# as14120_x31_fpga_power_conf.net
KiCad netlist of a schematic drawn in Altium Designer
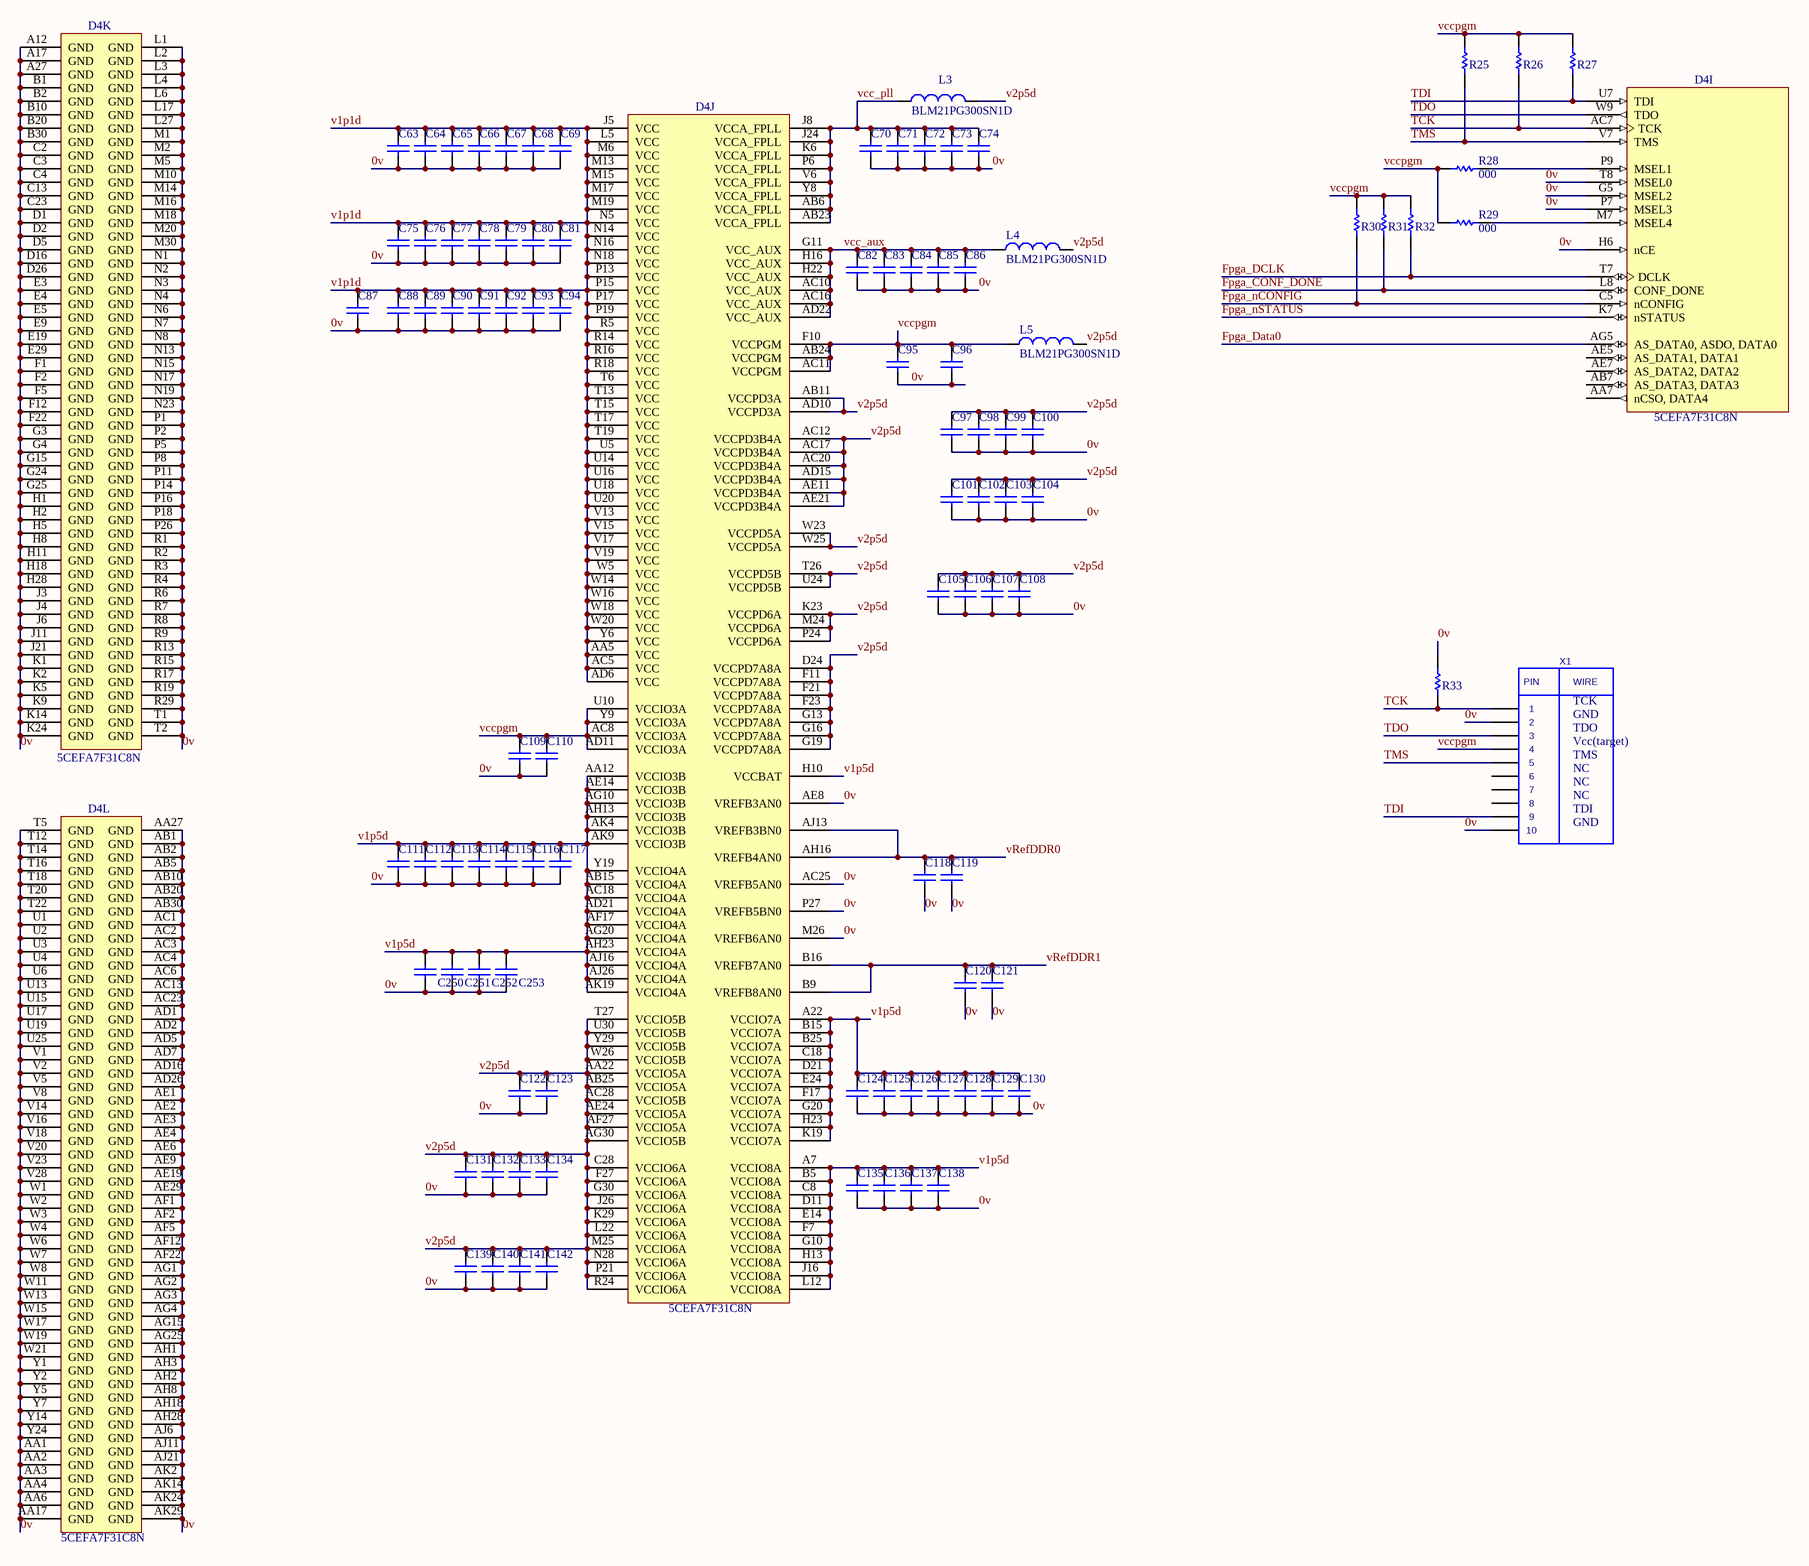
[diagram p0: as14120_x31_fpga_power_conf.SchDoc]

(export (version "E")
  (design (tool "Eeschema 10.0.6"))
  (components
    (comp (ref "C63")
      (value "CAP 1uF 10V 0402(1005)")
      (footprint "CAPC0402(1005)60_M")
      (description "CAP 1uF 10V ±20% 0402 (1005 Metric) Thickness 0.6mm SMD")
      (fields (field (name "TOLERANCE") "±20%"))
      (libsource (lib "as14120") (part "CAP_0402"))
    )
    (comp (ref "C64")
      (value "CAP 1uF 10V 0402(1005)")
      (footprint "CAPC0402(1005)60_M")
      (description "CAP 1uF 10V ±20% 0402 (1005 Metric) Thickness 0.6mm SMD")
      (fields (field (name "TOLERANCE") "±20%"))
      (libsource (lib "as14120") (part "CAP_0402"))
    )
    (comp (ref "C65")
      (value "CAP 1uF 10V 0402(1005)")
      (footprint "CAPC0402(1005)60_M")
      (description "CAP 1uF 10V ±20% 0402 (1005 Metric) Thickness 0.6mm SMD")
      (fields (field (name "TOLERANCE") "±20%"))
      (libsource (lib "as14120") (part "CAP_0402"))
    )
    (comp (ref "C66")
      (value "CAP 1uF 10V 0402(1005)")
      (footprint "CAPC0402(1005)60_M")
      (description "CAP 1uF 10V ±20% 0402 (1005 Metric) Thickness 0.6mm SMD")
      (fields (field (name "TOLERANCE") "±20%"))
      (libsource (lib "as14120") (part "CAP_0402"))
    )
    (comp (ref "C67")
      (value "CAP 1uF 10V 0402(1005)")
      (footprint "CAPC0402(1005)60_M")
      (description "CAP 1uF 10V ±20% 0402 (1005 Metric) Thickness 0.6mm SMD")
      (fields (field (name "TOLERANCE") "±20%"))
      (libsource (lib "as14120") (part "CAP_0402"))
    )
    (comp (ref "C68")
      (value "CAP 1uF 10V 0402(1005)")
      (footprint "CAPC0402(1005)60_M")
      (description "CAP 1uF 10V ±20% 0402 (1005 Metric) Thickness 0.6mm SMD")
      (fields (field (name "TOLERANCE") "±20%"))
      (libsource (lib "as14120") (part "CAP_0402"))
    )
    (comp (ref "C69")
      (value "CAP 1uF 10V 0402(1005)")
      (footprint "CAPC0402(1005)60_M")
      (description "CAP 1uF 10V ±20% 0402 (1005 Metric) Thickness 0.6mm SMD")
      (fields (field (name "TOLERANCE") "±20%"))
      (libsource (lib "as14120") (part "CAP_0402"))
    )
    (comp (ref "C70")
      (value "CAP 1uF 10V 0402(1005)")
      (footprint "CAPC0402(1005)60_M")
      (description "CAP 1uF 10V ±20% 0402 (1005 Metric) Thickness 0.6mm SMD")
      (fields (field (name "TOLERANCE") "±20%"))
      (libsource (lib "as14120") (part "CAP_0402"))
    )
    (comp (ref "C71")
      (value "CAP 1uF 10V 0402(1005)")
      (footprint "CAPC0402(1005)60_M")
      (description "CAP 1uF 10V ±20% 0402 (1005 Metric) Thickness 0.6mm SMD")
      (fields (field (name "TOLERANCE") "±20%"))
      (libsource (lib "as14120") (part "CAP_0402"))
    )
    (comp (ref "C72")
      (value "CAP 1uF 10V 0402(1005)")
      (footprint "CAPC0402(1005)60_M")
      (description "CAP 1uF 10V ±20% 0402 (1005 Metric) Thickness 0.6mm SMD")
      (fields (field (name "TOLERANCE") "±20%"))
      (libsource (lib "as14120") (part "CAP_0402"))
    )
    (comp (ref "C73")
      (value "CAP 1uF 10V 0402(1005)")
      (footprint "CAPC0402(1005)60_M")
      (description "CAP 1uF 10V ±20% 0402 (1005 Metric) Thickness 0.6mm SMD")
      (fields (field (name "TOLERANCE") "±20%"))
      (libsource (lib "as14120") (part "CAP_0402"))
    )
    (comp (ref "C74")
      (value "CAP 1uF 10V 0402(1005)")
      (footprint "CAPC0402(1005)60_M")
      (description "CAP 1uF 10V ±20% 0402 (1005 Metric) Thickness 0.6mm SMD")
      (fields (field (name "TOLERANCE") "±20%"))
      (libsource (lib "as14120") (part "CAP_0402"))
    )
    (comp (ref "C75")
      (value "CAP 1uF 10V 0402(1005)")
      (footprint "CAPC0402(1005)60_M")
      (description "CAP 1uF 10V ±20% 0402 (1005 Metric) Thickness 0.6mm SMD")
      (fields (field (name "TOLERANCE") "±20%"))
      (libsource (lib "as14120") (part "CAP_0402"))
    )
    (comp (ref "C76")
      (value "CAP 1uF 10V 0402(1005)")
      (footprint "CAPC0402(1005)60_M")
      (description "CAP 1uF 10V ±20% 0402 (1005 Metric) Thickness 0.6mm SMD")
      (fields (field (name "TOLERANCE") "±20%"))
      (libsource (lib "as14120") (part "CAP_0402"))
    )
    (comp (ref "C77")
      (value "CAP 1uF 10V 0402(1005)")
      (footprint "CAPC0402(1005)60_M")
      (description "CAP 1uF 10V ±20% 0402 (1005 Metric) Thickness 0.6mm SMD")
      (fields (field (name "TOLERANCE") "±20%"))
      (libsource (lib "as14120") (part "CAP_0402"))
    )
    (comp (ref "C78")
      (value "CAP 1uF 10V 0402(1005)")
      (footprint "CAPC0402(1005)60_M")
      (description "CAP 1uF 10V ±20% 0402 (1005 Metric) Thickness 0.6mm SMD")
      (fields (field (name "TOLERANCE") "±20%"))
      (libsource (lib "as14120") (part "CAP_0402"))
    )
    (comp (ref "C79")
      (value "CAP 1uF 10V 0402(1005)")
      (footprint "CAPC0402(1005)60_M")
      (description "CAP 1uF 10V ±20% 0402 (1005 Metric) Thickness 0.6mm SMD")
      (fields (field (name "TOLERANCE") "±20%"))
      (libsource (lib "as14120") (part "CAP_0402"))
    )
    (comp (ref "C80")
      (value "CAP 1uF 10V 0402(1005)")
      (footprint "CAPC0402(1005)60_M")
      (description "CAP 1uF 10V ±20% 0402 (1005 Metric) Thickness 0.6mm SMD")
      (fields (field (name "TOLERANCE") "±20%"))
      (libsource (lib "as14120") (part "CAP_0402"))
    )
    (comp (ref "C81")
      (value "CAP 1uF 10V 0402(1005)")
      (footprint "CAPC0402(1005)60_M")
      (description "CAP 1uF 10V ±20% 0402 (1005 Metric) Thickness 0.6mm SMD")
      (fields (field (name "TOLERANCE") "±20%"))
      (libsource (lib "as14120") (part "CAP_0402"))
    )
    (comp (ref "C82")
      (value "CAP 1uF 10V 0402(1005)")
      (footprint "CAPC0402(1005)60_M")
      (description "CAP 1uF 10V ±20% 0402 (1005 Metric) Thickness 0.6mm SMD")
      (fields (field (name "TOLERANCE") "±20%"))
      (libsource (lib "as14120") (part "CAP_0402"))
    )
    (comp (ref "C83")
      (value "CAP 1uF 10V 0402(1005)")
      (footprint "CAPC0402(1005)60_M")
      (description "CAP 1uF 10V ±20% 0402 (1005 Metric) Thickness 0.6mm SMD")
      (fields (field (name "TOLERANCE") "±20%"))
      (libsource (lib "as14120") (part "CAP_0402"))
    )
    (comp (ref "C84")
      (value "CAP 1uF 10V 0402(1005)")
      (footprint "CAPC0402(1005)60_M")
      (description "CAP 1uF 10V ±20% 0402 (1005 Metric) Thickness 0.6mm SMD")
      (fields (field (name "TOLERANCE") "±20%"))
      (libsource (lib "as14120") (part "CAP_0402"))
    )
    (comp (ref "C85")
      (value "CAP 1uF 10V 0402(1005)")
      (footprint "CAPC0402(1005)60_M")
      (description "CAP 1uF 10V ±20% 0402 (1005 Metric) Thickness 0.6mm SMD")
      (fields (field (name "TOLERANCE") "±20%"))
      (libsource (lib "as14120") (part "CAP_0402"))
    )
    (comp (ref "C86")
      (value "CAP 1uF 10V 0402(1005)")
      (footprint "CAPC0402(1005)60_M")
      (description "CAP 1uF 10V ±20% 0402 (1005 Metric) Thickness 0.6mm SMD")
      (fields (field (name "TOLERANCE") "±20%"))
      (libsource (lib "as14120") (part "CAP_0402"))
    )
    (comp (ref "C87")
      (value "CAP 1uF 10V 0402(1005)")
      (footprint "CAPC0402(1005)60_M")
      (description "CAP 1uF 10V ±20% 0402 (1005 Metric) Thickness 0.6mm SMD")
      (fields (field (name "TOLERANCE") "±20%"))
      (libsource (lib "as14120") (part "CAP_0402"))
    )
    (comp (ref "C88")
      (value "CAP 1uF 10V 0402(1005)")
      (footprint "CAPC0402(1005)60_M")
      (description "CAP 1uF 10V ±20% 0402 (1005 Metric) Thickness 0.6mm SMD")
      (fields (field (name "TOLERANCE") "±20%"))
      (libsource (lib "as14120") (part "CAP_0402"))
    )
    (comp (ref "C89")
      (value "CAP 1uF 10V 0402(1005)")
      (footprint "CAPC0402(1005)60_M")
      (description "CAP 1uF 10V ±20% 0402 (1005 Metric) Thickness 0.6mm SMD")
      (fields (field (name "TOLERANCE") "±20%"))
      (libsource (lib "as14120") (part "CAP_0402"))
    )
    (comp (ref "C90")
      (value "CAP 1uF 10V 0402(1005)")
      (footprint "CAPC0402(1005)60_M")
      (description "CAP 1uF 10V ±20% 0402 (1005 Metric) Thickness 0.6mm SMD")
      (fields (field (name "TOLERANCE") "±20%"))
      (libsource (lib "as14120") (part "CAP_0402"))
    )
    (comp (ref "C91")
      (value "CAP 1uF 10V 0402(1005)")
      (footprint "CAPC0402(1005)60_M")
      (description "CAP 1uF 10V ±20% 0402 (1005 Metric) Thickness 0.6mm SMD")
      (fields (field (name "TOLERANCE") "±20%"))
      (libsource (lib "as14120") (part "CAP_0402"))
    )
    (comp (ref "C92")
      (value "CAP 1uF 10V 0402(1005)")
      (footprint "CAPC0402(1005)60_M")
      (description "CAP 1uF 10V ±20% 0402 (1005 Metric) Thickness 0.6mm SMD")
      (fields (field (name "TOLERANCE") "±20%"))
      (libsource (lib "as14120") (part "CAP_0402"))
    )
    (comp (ref "C93")
      (value "CAP 1uF 10V 0402(1005)")
      (footprint "CAPC0402(1005)60_M")
      (description "CAP 1uF 10V ±20% 0402 (1005 Metric) Thickness 0.6mm SMD")
      (fields (field (name "TOLERANCE") "±20%"))
      (libsource (lib "as14120") (part "CAP_0402"))
    )
    (comp (ref "C94")
      (value "CAP 1uF 10V 0402(1005)")
      (footprint "CAPC0402(1005)60_M")
      (description "CAP 1uF 10V ±20% 0402 (1005 Metric) Thickness 0.6mm SMD")
      (fields (field (name "TOLERANCE") "±20%"))
      (libsource (lib "as14120") (part "CAP_0402"))
    )
    (comp (ref "C95")
      (value "CAP 1uF 10V 0402(1005)")
      (footprint "CAPC0402(1005)60_M")
      (description "CAP 1uF 10V ±20% 0402 (1005 Metric) Thickness 0.6mm SMD")
      (fields (field (name "TOLERANCE") "±20%"))
      (libsource (lib "as14120") (part "CAP_0402"))
    )
    (comp (ref "C96")
      (value "CAP 1uF 10V 0402(1005)")
      (footprint "CAPC0402(1005)60_M")
      (description "CAP 1uF 10V ±20% 0402 (1005 Metric) Thickness 0.6mm SMD")
      (fields (field (name "TOLERANCE") "±20%"))
      (libsource (lib "as14120") (part "CAP_0402"))
    )
    (comp (ref "C97")
      (value "CAP 1uF 10V 0402(1005)")
      (footprint "CAPC0402(1005)60_M")
      (description "CAP 1uF 10V ±20% 0402 (1005 Metric) Thickness 0.6mm SMD")
      (fields (field (name "TOLERANCE") "±20%"))
      (libsource (lib "as14120") (part "CAP_0402"))
    )
    (comp (ref "C98")
      (value "CAP 1uF 10V 0402(1005)")
      (footprint "CAPC0402(1005)60_M")
      (description "CAP 1uF 10V ±20% 0402 (1005 Metric) Thickness 0.6mm SMD")
      (fields (field (name "TOLERANCE") "±20%"))
      (libsource (lib "as14120") (part "CAP_0402"))
    )
    (comp (ref "C99")
      (value "CAP 1uF 10V 0402(1005)")
      (footprint "CAPC0402(1005)60_M")
      (description "CAP 1uF 10V ±20% 0402 (1005 Metric) Thickness 0.6mm SMD")
      (fields (field (name "TOLERANCE") "±20%"))
      (libsource (lib "as14120") (part "CAP_0402"))
    )
    (comp (ref "C100")
      (value "CAP 1uF 10V 0402(1005)")
      (footprint "CAPC0402(1005)60_M")
      (description "CAP 1uF 10V ±20% 0402 (1005 Metric) Thickness 0.6mm SMD")
      (fields (field (name "TOLERANCE") "±20%"))
      (libsource (lib "as14120") (part "CAP_0402"))
    )
    (comp (ref "C101")
      (value "CAP 1uF 10V 0402(1005)")
      (footprint "CAPC0402(1005)60_M")
      (description "CAP 1uF 10V ±20% 0402 (1005 Metric) Thickness 0.6mm SMD")
      (fields (field (name "TOLERANCE") "±20%"))
      (libsource (lib "as14120") (part "CAP_0402"))
    )
    (comp (ref "C102")
      (value "CAP 1uF 10V 0402(1005)")
      (footprint "CAPC0402(1005)60_M")
      (description "CAP 1uF 10V ±20% 0402 (1005 Metric) Thickness 0.6mm SMD")
      (fields (field (name "TOLERANCE") "±20%"))
      (libsource (lib "as14120") (part "CAP_0402"))
    )
    (comp (ref "C103")
      (value "CAP 1uF 10V 0402(1005)")
      (footprint "CAPC0402(1005)60_M")
      (description "CAP 1uF 10V ±20% 0402 (1005 Metric) Thickness 0.6mm SMD")
      (fields (field (name "TOLERANCE") "±20%"))
      (libsource (lib "as14120") (part "CAP_0402"))
    )
    (comp (ref "C104")
      (value "CAP 1uF 10V 0402(1005)")
      (footprint "CAPC0402(1005)60_M")
      (description "CAP 1uF 10V ±20% 0402 (1005 Metric) Thickness 0.6mm SMD")
      (fields (field (name "TOLERANCE") "±20%"))
      (libsource (lib "as14120") (part "CAP_0402"))
    )
    (comp (ref "C105")
      (value "CAP 1uF 10V 0402(1005)")
      (footprint "CAPC0402(1005)60_M")
      (description "CAP 1uF 10V ±20% 0402 (1005 Metric) Thickness 0.6mm SMD")
      (fields (field (name "TOLERANCE") "±20%"))
      (libsource (lib "as14120") (part "CAP_0402"))
    )
    (comp (ref "C106")
      (value "CAP 1uF 10V 0402(1005)")
      (footprint "CAPC0402(1005)60_M")
      (description "CAP 1uF 10V ±20% 0402 (1005 Metric) Thickness 0.6mm SMD")
      (fields (field (name "TOLERANCE") "±20%"))
      (libsource (lib "as14120") (part "CAP_0402"))
    )
    (comp (ref "C107")
      (value "CAP 1uF 10V 0402(1005)")
      (footprint "CAPC0402(1005)60_M")
      (description "CAP 1uF 10V ±20% 0402 (1005 Metric) Thickness 0.6mm SMD")
      (fields (field (name "TOLERANCE") "±20%"))
      (libsource (lib "as14120") (part "CAP_0402"))
    )
    (comp (ref "C108")
      (value "CAP 1uF 10V 0402(1005)")
      (footprint "CAPC0402(1005)60_M")
      (description "CAP 1uF 10V ±20% 0402 (1005 Metric) Thickness 0.6mm SMD")
      (fields (field (name "TOLERANCE") "±20%"))
      (libsource (lib "as14120") (part "CAP_0402"))
    )
    (comp (ref "C109")
      (value "CAP 1uF 10V 0402(1005)")
      (footprint "CAPC0402(1005)60_M")
      (description "CAP 1uF 10V ±20% 0402 (1005 Metric) Thickness 0.6mm SMD")
      (fields (field (name "TOLERANCE") "±20%"))
      (libsource (lib "as14120") (part "CAP_0402"))
    )
    (comp (ref "C110")
      (value "CAP 1uF 10V 0402(1005)")
      (footprint "CAPC0402(1005)60_M")
      (description "CAP 1uF 10V ±20% 0402 (1005 Metric) Thickness 0.6mm SMD")
      (fields (field (name "TOLERANCE") "±20%"))
      (libsource (lib "as14120") (part "CAP_0402"))
    )
    (comp (ref "C111")
      (value "CAP 1uF 10V 0402(1005)")
      (footprint "CAPC0402(1005)60_M")
      (description "CAP 1uF 10V ±20% 0402 (1005 Metric) Thickness 0.6mm SMD")
      (fields (field (name "TOLERANCE") "±20%"))
      (libsource (lib "as14120") (part "CAP_0402"))
    )
    (comp (ref "C112")
      (value "CAP 1uF 10V 0402(1005)")
      (footprint "CAPC0402(1005)60_M")
      (description "CAP 1uF 10V ±20% 0402 (1005 Metric) Thickness 0.6mm SMD")
      (fields (field (name "TOLERANCE") "±20%"))
      (libsource (lib "as14120") (part "CAP_0402"))
    )
    (comp (ref "C113")
      (value "CAP 1uF 10V 0402(1005)")
      (footprint "CAPC0402(1005)60_M")
      (description "CAP 1uF 10V ±20% 0402 (1005 Metric) Thickness 0.6mm SMD")
      (fields (field (name "TOLERANCE") "±20%"))
      (libsource (lib "as14120") (part "CAP_0402"))
    )
    (comp (ref "C114")
      (value "CAP 1uF 10V 0402(1005)")
      (footprint "CAPC0402(1005)60_M")
      (description "CAP 1uF 10V ±20% 0402 (1005 Metric) Thickness 0.6mm SMD")
      (fields (field (name "TOLERANCE") "±20%"))
      (libsource (lib "as14120") (part "CAP_0402"))
    )
    (comp (ref "C115")
      (value "CAP 1uF 10V 0402(1005)")
      (footprint "CAPC0402(1005)60_M")
      (description "CAP 1uF 10V ±20% 0402 (1005 Metric) Thickness 0.6mm SMD")
      (fields (field (name "TOLERANCE") "±20%"))
      (libsource (lib "as14120") (part "CAP_0402"))
    )
    (comp (ref "C116")
      (value "CAP 1uF 10V 0402(1005)")
      (footprint "CAPC0402(1005)60_M")
      (description "CAP 1uF 10V ±20% 0402 (1005 Metric) Thickness 0.6mm SMD")
      (fields (field (name "TOLERANCE") "±20%"))
      (libsource (lib "as14120") (part "CAP_0402"))
    )
    (comp (ref "C117")
      (value "CAP 1uF 10V 0402(1005)")
      (footprint "CAPC0402(1005)60_M")
      (description "CAP 1uF 10V ±20% 0402 (1005 Metric) Thickness 0.6mm SMD")
      (fields (field (name "TOLERANCE") "±20%"))
      (libsource (lib "as14120") (part "CAP_0402"))
    )
    (comp (ref "C118")
      (value "CAP 1uF 10V 0402(1005)")
      (footprint "CAPC0402(1005)60_M")
      (description "CAP 1uF 10V ±20% 0402 (1005 Metric) Thickness 0.6mm SMD")
      (fields (field (name "TOLERANCE") "±20%"))
      (libsource (lib "as14120") (part "CAP_0402"))
    )
    (comp (ref "C119")
      (value "CAP 1uF 10V 0402(1005)")
      (footprint "CAPC0402(1005)60_M")
      (description "CAP 1uF 10V ±20% 0402 (1005 Metric) Thickness 0.6mm SMD")
      (fields (field (name "TOLERANCE") "±20%"))
      (libsource (lib "as14120") (part "CAP_0402"))
    )
    (comp (ref "C120")
      (value "CAP 1uF 10V 0402(1005)")
      (footprint "CAPC0402(1005)60_M")
      (description "CAP 1uF 10V ±20% 0402 (1005 Metric) Thickness 0.6mm SMD")
      (fields (field (name "TOLERANCE") "±20%"))
      (libsource (lib "as14120") (part "CAP_0402"))
    )
    (comp (ref "C121")
      (value "CAP 1uF 10V 0402(1005)")
      (footprint "CAPC0402(1005)60_M")
      (description "CAP 1uF 10V ±20% 0402 (1005 Metric) Thickness 0.6mm SMD")
      (fields (field (name "TOLERANCE") "±20%"))
      (libsource (lib "as14120") (part "CAP_0402"))
    )
    (comp (ref "C122")
      (value "CAP 1uF 10V 0402(1005)")
      (footprint "CAPC0402(1005)60_M")
      (description "CAP 1uF 10V ±20% 0402 (1005 Metric) Thickness 0.6mm SMD")
      (fields (field (name "TOLERANCE") "±20%"))
      (libsource (lib "as14120") (part "CAP_0402"))
    )
    (comp (ref "C123")
      (value "CAP 1uF 10V 0402(1005)")
      (footprint "CAPC0402(1005)60_M")
      (description "CAP 1uF 10V ±20% 0402 (1005 Metric) Thickness 0.6mm SMD")
      (fields (field (name "TOLERANCE") "±20%"))
      (libsource (lib "as14120") (part "CAP_0402"))
    )
    (comp (ref "C124")
      (value "CAP 1uF 10V 0402(1005)")
      (footprint "CAPC0402(1005)60_M")
      (description "CAP 1uF 10V ±20% 0402 (1005 Metric) Thickness 0.6mm SMD")
      (fields (field (name "TOLERANCE") "±20%"))
      (libsource (lib "as14120") (part "CAP_0402"))
    )
    (comp (ref "C125")
      (value "CAP 1uF 10V 0402(1005)")
      (footprint "CAPC0402(1005)60_M")
      (description "CAP 1uF 10V ±20% 0402 (1005 Metric) Thickness 0.6mm SMD")
      (fields (field (name "TOLERANCE") "±20%"))
      (libsource (lib "as14120") (part "CAP_0402"))
    )
    (comp (ref "C126")
      (value "CAP 1uF 10V 0402(1005)")
      (footprint "CAPC0402(1005)60_M")
      (description "CAP 1uF 10V ±20% 0402 (1005 Metric) Thickness 0.6mm SMD")
      (fields (field (name "TOLERANCE") "±20%"))
      (libsource (lib "as14120") (part "CAP_0402"))
    )
    (comp (ref "C127")
      (value "CAP 1uF 10V 0402(1005)")
      (footprint "CAPC0402(1005)60_M")
      (description "CAP 1uF 10V ±20% 0402 (1005 Metric) Thickness 0.6mm SMD")
      (fields (field (name "TOLERANCE") "±20%"))
      (libsource (lib "as14120") (part "CAP_0402"))
    )
    (comp (ref "C128")
      (value "CAP 1uF 10V 0402(1005)")
      (footprint "CAPC0402(1005)60_M")
      (description "CAP 1uF 10V ±20% 0402 (1005 Metric) Thickness 0.6mm SMD")
      (fields (field (name "TOLERANCE") "±20%"))
      (libsource (lib "as14120") (part "CAP_0402"))
    )
    (comp (ref "C129")
      (value "CAP 1uF 10V 0402(1005)")
      (footprint "CAPC0402(1005)60_M")
      (description "CAP 1uF 10V ±20% 0402 (1005 Metric) Thickness 0.6mm SMD")
      (fields (field (name "TOLERANCE") "±20%"))
      (libsource (lib "as14120") (part "CAP_0402"))
    )
    (comp (ref "C130")
      (value "CAP 1uF 10V 0402(1005)")
      (footprint "CAPC0402(1005)60_M")
      (description "CAP 1uF 10V ±20% 0402 (1005 Metric) Thickness 0.6mm SMD")
      (fields (field (name "TOLERANCE") "±20%"))
      (libsource (lib "as14120") (part "CAP_0402"))
    )
    (comp (ref "C131")
      (value "CAP 1uF 10V 0402(1005)")
      (footprint "CAPC0402(1005)60_M")
      (description "CAP 1uF 10V ±20% 0402 (1005 Metric) Thickness 0.6mm SMD")
      (fields (field (name "TOLERANCE") "±20%"))
      (libsource (lib "as14120") (part "CAP_0402"))
    )
    (comp (ref "C132")
      (value "CAP 1uF 10V 0402(1005)")
      (footprint "CAPC0402(1005)60_M")
      (description "CAP 1uF 10V ±20% 0402 (1005 Metric) Thickness 0.6mm SMD")
      (fields (field (name "TOLERANCE") "±20%"))
      (libsource (lib "as14120") (part "CAP_0402"))
    )
    (comp (ref "C133")
      (value "CAP 1uF 10V 0402(1005)")
      (footprint "CAPC0402(1005)60_M")
      (description "CAP 1uF 10V ±20% 0402 (1005 Metric) Thickness 0.6mm SMD")
      (fields (field (name "TOLERANCE") "±20%"))
      (libsource (lib "as14120") (part "CAP_0402"))
    )
    (comp (ref "C134")
      (value "CAP 1uF 10V 0402(1005)")
      (footprint "CAPC0402(1005)60_M")
      (description "CAP 1uF 10V ±20% 0402 (1005 Metric) Thickness 0.6mm SMD")
      (fields (field (name "TOLERANCE") "±20%"))
      (libsource (lib "as14120") (part "CAP_0402"))
    )
    (comp (ref "C135")
      (value "CAP 1uF 10V 0402(1005)")
      (footprint "CAPC0402(1005)60_M")
      (description "CAP 1uF 10V ±20% 0402 (1005 Metric) Thickness 0.6mm SMD")
      (fields (field (name "TOLERANCE") "±20%"))
      (libsource (lib "as14120") (part "CAP_0402"))
    )
    (comp (ref "C136")
      (value "CAP 1uF 10V 0402(1005)")
      (footprint "CAPC0402(1005)60_M")
      (description "CAP 1uF 10V ±20% 0402 (1005 Metric) Thickness 0.6mm SMD")
      (fields (field (name "TOLERANCE") "±20%"))
      (libsource (lib "as14120") (part "CAP_0402"))
    )
    (comp (ref "C137")
      (value "CAP 1uF 10V 0402(1005)")
      (footprint "CAPC0402(1005)60_M")
      (description "CAP 1uF 10V ±20% 0402 (1005 Metric) Thickness 0.6mm SMD")
      (fields (field (name "TOLERANCE") "±20%"))
      (libsource (lib "as14120") (part "CAP_0402"))
    )
    (comp (ref "C138")
      (value "CAP 1uF 10V 0402(1005)")
      (footprint "CAPC0402(1005)60_M")
      (description "CAP 1uF 10V ±20% 0402 (1005 Metric) Thickness 0.6mm SMD")
      (fields (field (name "TOLERANCE") "±20%"))
      (libsource (lib "as14120") (part "CAP_0402"))
    )
    (comp (ref "C139")
      (value "CAP 1uF 10V 0402(1005)")
      (footprint "CAPC0402(1005)60_M")
      (description "CAP 1uF 10V ±20% 0402 (1005 Metric) Thickness 0.6mm SMD")
      (fields (field (name "TOLERANCE") "±20%"))
      (libsource (lib "as14120") (part "CAP_0402"))
    )
    (comp (ref "C140")
      (value "CAP 1uF 10V 0402(1005)")
      (footprint "CAPC0402(1005)60_M")
      (description "CAP 1uF 10V ±20% 0402 (1005 Metric) Thickness 0.6mm SMD")
      (fields (field (name "TOLERANCE") "±20%"))
      (libsource (lib "as14120") (part "CAP_0402"))
    )
    (comp (ref "C141")
      (value "CAP 1uF 10V 0402(1005)")
      (footprint "CAPC0402(1005)60_M")
      (description "CAP 1uF 10V ±20% 0402 (1005 Metric) Thickness 0.6mm SMD")
      (fields (field (name "TOLERANCE") "±20%"))
      (libsource (lib "as14120") (part "CAP_0402"))
    )
    (comp (ref "C142")
      (value "CAP 1uF 10V 0402(1005)")
      (footprint "CAPC0402(1005)60_M")
      (description "CAP 1uF 10V ±20% 0402 (1005 Metric) Thickness 0.6mm SMD")
      (fields (field (name "TOLERANCE") "±20%"))
      (libsource (lib "as14120") (part "CAP_0402"))
    )
    (comp (ref "C250")
      (value "CAP 1uF 10V 0402(1005)")
      (footprint "CAPC0402(1005)60_M")
      (description "CAP 1uF 10V ±20% 0402 (1005 Metric) Thickness 0.6mm SMD")
      (fields (field (name "TOLERANCE") "±20%"))
      (libsource (lib "as14120") (part "CAP_0402"))
    )
    (comp (ref "C251")
      (value "CAP 1uF 10V 0402(1005)")
      (footprint "CAPC0402(1005)60_M")
      (description "CAP 1uF 10V ±20% 0402 (1005 Metric) Thickness 0.6mm SMD")
      (fields (field (name "TOLERANCE") "±20%"))
      (libsource (lib "as14120") (part "CAP_0402"))
    )
    (comp (ref "C252")
      (value "CAP 1uF 10V 0402(1005)")
      (footprint "CAPC0402(1005)60_M")
      (description "CAP 1uF 10V ±20% 0402 (1005 Metric) Thickness 0.6mm SMD")
      (fields (field (name "TOLERANCE") "±20%"))
      (libsource (lib "as14120") (part "CAP_0402"))
    )
    (comp (ref "C253")
      (value "CAP 1uF 10V 0402(1005)")
      (footprint "CAPC0402(1005)60_M")
      (description "CAP 1uF 10V ±20% 0402 (1005 Metric) Thickness 0.6mm SMD")
      (fields (field (name "TOLERANCE") "±20%"))
      (libsource (lib "as14120") (part "CAP_0402"))
    )
    (comp (ref "D4")
      (value "5CEFA7F31C8N")
      (footprint "ALTR-896-FBGA-2000A")
      (fields (field (name "MANUFACTURER") "Altera"))
      (libsource (lib "Altera Cyclone V E") (part "5CEFA7F31C8N"))
    )
    (comp (ref "L3")
      (value "BLM21PG300SN1D")
      (footprint "CAPC0805(2012)100_N")
      (libsource (lib "as14120") (part "Ferrite_beat"))
    )
    (comp (ref "L4")
      (value "BLM21PG300SN1D")
      (footprint "CAPC0805(2012)100_N")
      (libsource (lib "as14120") (part "Ferrite_beat"))
    )
    (comp (ref "L5")
      (value "BLM21PG300SN1D")
      (footprint "CAPC0805(2012)100_N")
      (libsource (lib "as14120") (part "Ferrite_beat"))
    )
    (comp (ref "R25")
      (value "1K 5% 0603(1608)")
      (footprint "RESC0603(1608)_L")
      (description "1K 0.1W 5% 0603 (1608 Metric)  SMD")
      (fields (field (name "TOLERANCE") "5 %") (field (name "POWER") "0.1 W"))
      (libsource (lib "as14120") (part "RES_0603"))
    )
    (comp (ref "R26")
      (value "1K 5% 0603(1608)")
      (footprint "RESC0603(1608)_L")
      (description "1K 0.1W 5% 0603 (1608 Metric)  SMD")
      (fields (field (name "TOLERANCE") "5 %") (field (name "POWER") "0.1 W"))
      (libsource (lib "as14120") (part "RES_0603"))
    )
    (comp (ref "R27")
      (value "1K 5% 0603(1608)")
      (footprint "RESC0603(1608)_L")
      (description "1K 0.1W 5% 0603 (1608 Metric)  SMD")
      (fields (field (name "TOLERANCE") "5 %") (field (name "POWER") "0.1 W"))
      (libsource (lib "as14120") (part "RES_0603"))
    )
    (comp (ref "R28")
      (value "000")
      (footprint "RESC0603(1608)_L")
      (description "1K 0.1W 5% 0603 (1608 Metric)  SMD")
      (fields (field (name "TOLERANCE") "5 %") (field (name "POWER") "0.1 W"))
      (libsource (lib "as14120") (part "RES_0603"))
    )
    (comp (ref "R29")
      (value "000")
      (footprint "RESC0603(1608)_L")
      (description "1K 0.1W 5% 0603 (1608 Metric)  SMD")
      (fields (field (name "TOLERANCE") "5 %") (field (name "POWER") "0.1 W"))
      (libsource (lib "as14120") (part "RES_0603"))
    )
    (comp (ref "R30")
      (value "1K 5% 0603(1608)")
      (footprint "RESC0603(1608)_L")
      (description "1K 0.1W 5% 0603 (1608 Metric)  SMD")
      (fields (field (name "TOLERANCE") "5 %") (field (name "POWER") "0.1 W"))
      (libsource (lib "as14120") (part "RES_0603"))
    )
    (comp (ref "R31")
      (value "1K 5% 0603(1608)")
      (footprint "RESC0603(1608)_L")
      (description "1K 0.1W 5% 0603 (1608 Metric)  SMD")
      (fields (field (name "TOLERANCE") "5 %") (field (name "POWER") "0.1 W"))
      (libsource (lib "as14120") (part "RES_0603"))
    )
    (comp (ref "R32")
      (value "1K 5% 0603(1608)")
      (footprint "RESC0603(1608)_L")
      (description "1K 0.1W 5% 0603 (1608 Metric)  SMD")
      (fields (field (name "TOLERANCE") "5 %") (field (name "POWER") "0.1 W"))
      (libsource (lib "as14120") (part "RES_0603"))
    )
    (comp (ref "R33")
      (value "1K 5% 0603(1608)")
      (footprint "RESC0603(1608)_L")
      (description "1K 0.1W 5% 0603 (1608 Metric)  SMD")
      (fields (field (name "TOLERANCE") "5 %") (field (name "POWER") "0.1 W"))
      (libsource (lib "as14120") (part "RES_0603"))
    )
    (comp (ref "X1") (value "IDC10") (footprint "IDC10M") (libsource (lib "alexsb") (part "IDC10")))
  )
  (nets
    (net (code "1") (name "/0v") (class "Default")
      (node (ref "C100") (pin "1") (pinfunction "1_1") (pintype "passive"))
      (node (ref "C101") (pin "1") (pinfunction "1_1") (pintype "passive"))
      (node (ref "C102") (pin "1") (pinfunction "1_1") (pintype "passive"))
      (node (ref "C103") (pin "1") (pinfunction "1_1") (pintype "passive"))
      (node (ref "C104") (pin "1") (pinfunction "1_1") (pintype "passive"))
      (node (ref "C105") (pin "1") (pinfunction "1_1") (pintype "passive"))
      (node (ref "C106") (pin "1") (pinfunction "1_1") (pintype "passive"))
      (node (ref "C107") (pin "1") (pinfunction "1_1") (pintype "passive"))
      (node (ref "C108") (pin "1") (pinfunction "1_1") (pintype "passive"))
      (node (ref "C109") (pin "1") (pinfunction "1_1") (pintype "passive"))
      (node (ref "C110") (pin "1") (pinfunction "1_1") (pintype "passive"))
      (node (ref "C111") (pin "1") (pinfunction "1_1") (pintype "passive"))
      (node (ref "C112") (pin "1") (pinfunction "1_1") (pintype "passive"))
      (node (ref "C113") (pin "1") (pinfunction "1_1") (pintype "passive"))
      (node (ref "C114") (pin "1") (pinfunction "1_1") (pintype "passive"))
      (node (ref "C115") (pin "1") (pinfunction "1_1") (pintype "passive"))
      (node (ref "C116") (pin "1") (pinfunction "1_1") (pintype "passive"))
      (node (ref "C117") (pin "1") (pinfunction "1_1") (pintype "passive"))
      (node (ref "C118") (pin "1") (pinfunction "1_1") (pintype "passive"))
      (node (ref "C119") (pin "1") (pinfunction "1_1") (pintype "passive"))
      (node (ref "C120") (pin "1") (pinfunction "1_1") (pintype "passive"))
      (node (ref "C121") (pin "1") (pinfunction "1_1") (pintype "passive"))
      (node (ref "C122") (pin "1") (pinfunction "1_1") (pintype "passive"))
      (node (ref "C123") (pin "1") (pinfunction "1_1") (pintype "passive"))
      (node (ref "C124") (pin "1") (pinfunction "1_1") (pintype "passive"))
      (node (ref "C125") (pin "1") (pinfunction "1_1") (pintype "passive"))
      (node (ref "C126") (pin "1") (pinfunction "1_1") (pintype "passive"))
      (node (ref "C127") (pin "1") (pinfunction "1_1") (pintype "passive"))
      (node (ref "C128") (pin "1") (pinfunction "1_1") (pintype "passive"))
      (node (ref "C129") (pin "1") (pinfunction "1_1") (pintype "passive"))
      (node (ref "C130") (pin "1") (pinfunction "1_1") (pintype "passive"))
      (node (ref "C131") (pin "1") (pinfunction "1_1") (pintype "passive"))
      (node (ref "C132") (pin "1") (pinfunction "1_1") (pintype "passive"))
      (node (ref "C133") (pin "1") (pinfunction "1_1") (pintype "passive"))
      (node (ref "C134") (pin "1") (pinfunction "1_1") (pintype "passive"))
      (node (ref "C135") (pin "1") (pinfunction "1_1") (pintype "passive"))
      (node (ref "C136") (pin "1") (pinfunction "1_1") (pintype "passive"))
      (node (ref "C137") (pin "1") (pinfunction "1_1") (pintype "passive"))
      (node (ref "C138") (pin "1") (pinfunction "1_1") (pintype "passive"))
      (node (ref "C139") (pin "1") (pinfunction "1_1") (pintype "passive"))
      (node (ref "C140") (pin "1") (pinfunction "1_1") (pintype "passive"))
      (node (ref "C141") (pin "1") (pinfunction "1_1") (pintype "passive"))
      (node (ref "C142") (pin "1") (pinfunction "1_1") (pintype "passive"))
      (node (ref "C250") (pin "1") (pinfunction "1_1") (pintype "passive"))
      (node (ref "C251") (pin "1") (pinfunction "1_1") (pintype "passive"))
      (node (ref "C252") (pin "1") (pinfunction "1_1") (pintype "passive"))
      (node (ref "C253") (pin "1") (pinfunction "1_1") (pintype "passive"))
      (node (ref "C63") (pin "1") (pinfunction "1_1") (pintype "passive"))
      (node (ref "C64") (pin "1") (pinfunction "1_1") (pintype "passive"))
      (node (ref "C65") (pin "1") (pinfunction "1_1") (pintype "passive"))
      (node (ref "C66") (pin "1") (pinfunction "1_1") (pintype "passive"))
      (node (ref "C67") (pin "1") (pinfunction "1_1") (pintype "passive"))
      (node (ref "C68") (pin "1") (pinfunction "1_1") (pintype "passive"))
      (node (ref "C69") (pin "1") (pinfunction "1_1") (pintype "passive"))
      (node (ref "C70") (pin "1") (pinfunction "1_1") (pintype "passive"))
      (node (ref "C71") (pin "1") (pinfunction "1_1") (pintype "passive"))
      (node (ref "C72") (pin "1") (pinfunction "1_1") (pintype "passive"))
      (node (ref "C73") (pin "1") (pinfunction "1_1") (pintype "passive"))
      (node (ref "C74") (pin "1") (pinfunction "1_1") (pintype "passive"))
      (node (ref "C75") (pin "1") (pinfunction "1_1") (pintype "passive"))
      (node (ref "C76") (pin "1") (pinfunction "1_1") (pintype "passive"))
      (node (ref "C77") (pin "1") (pinfunction "1_1") (pintype "passive"))
      (node (ref "C78") (pin "1") (pinfunction "1_1") (pintype "passive"))
      (node (ref "C79") (pin "1") (pinfunction "1_1") (pintype "passive"))
      (node (ref "C80") (pin "1") (pinfunction "1_1") (pintype "passive"))
      (node (ref "C81") (pin "1") (pinfunction "1_1") (pintype "passive"))
      (node (ref "C82") (pin "1") (pinfunction "1_1") (pintype "passive"))
      (node (ref "C83") (pin "1") (pinfunction "1_1") (pintype "passive"))
      (node (ref "C84") (pin "1") (pinfunction "1_1") (pintype "passive"))
      (node (ref "C85") (pin "1") (pinfunction "1_1") (pintype "passive"))
      (node (ref "C86") (pin "1") (pinfunction "1_1") (pintype "passive"))
      (node (ref "C87") (pin "1") (pinfunction "1_1") (pintype "passive"))
      (node (ref "C88") (pin "1") (pinfunction "1_1") (pintype "passive"))
      (node (ref "C89") (pin "1") (pinfunction "1_1") (pintype "passive"))
      (node (ref "C90") (pin "1") (pinfunction "1_1") (pintype "passive"))
      (node (ref "C91") (pin "1") (pinfunction "1_1") (pintype "passive"))
      (node (ref "C92") (pin "1") (pinfunction "1_1") (pintype "passive"))
      (node (ref "C93") (pin "1") (pinfunction "1_1") (pintype "passive"))
      (node (ref "C94") (pin "1") (pinfunction "1_1") (pintype "passive"))
      (node (ref "C95") (pin "1") (pinfunction "1_1") (pintype "passive"))
      (node (ref "C96") (pin "1") (pinfunction "1_1") (pintype "passive"))
      (node (ref "C97") (pin "1") (pinfunction "1_1") (pintype "passive"))
      (node (ref "C98") (pin "1") (pinfunction "1_1") (pintype "passive"))
      (node (ref "C99") (pin "1") (pinfunction "1_1") (pintype "passive"))
      (node (ref "D4") (pin "A12") (pinfunction "GND_A12") (pintype "power_in"))
      (node (ref "D4") (pin "A17") (pinfunction "GND_A17") (pintype "power_in"))
      (node (ref "D4") (pin "A27") (pinfunction "GND_A27") (pintype "power_in"))
      (node (ref "D4") (pin "AA1") (pinfunction "GND_AA1") (pintype "power_in"))
      (node (ref "D4") (pin "AA17") (pinfunction "GND_AA17") (pintype "power_in"))
      (node (ref "D4") (pin "AA2") (pinfunction "GND_AA2") (pintype "power_in"))
      (node (ref "D4") (pin "AA27") (pinfunction "GND_AA27") (pintype "power_in"))
      (node (ref "D4") (pin "AA3") (pinfunction "GND_AA3") (pintype "power_in"))
      (node (ref "D4") (pin "AA4") (pinfunction "GND_AA4") (pintype "power_in"))
      (node (ref "D4") (pin "AA6") (pinfunction "GND_AA6") (pintype "power_in"))
      (node (ref "D4") (pin "AB1") (pinfunction "GND_AB1") (pintype "power_in"))
      (node (ref "D4") (pin "AB10") (pinfunction "GND_AB10") (pintype "power_in"))
      (node (ref "D4") (pin "AB2") (pinfunction "GND_AB2") (pintype "power_in"))
      (node (ref "D4") (pin "AB20") (pinfunction "GND_AB20") (pintype "power_in"))
      (node (ref "D4") (pin "AB30") (pinfunction "GND_AB30") (pintype "power_in"))
      (node (ref "D4") (pin "AB5") (pinfunction "GND_AB5") (pintype "power_in"))
      (node (ref "D4") (pin "AC1") (pinfunction "GND_AC1") (pintype "power_in"))
      (node (ref "D4") (pin "AC13") (pinfunction "GND_AC13") (pintype "power_in"))
      (node (ref "D4") (pin "AC2") (pinfunction "GND_AC2") (pintype "power_in"))
      (node (ref "D4") (pin "AC23") (pinfunction "GND_AC23") (pintype "power_in"))
      (node (ref "D4") (pin "AC25") (pinfunction "VREFB5AN0_AC25") (pintype "power_in"))
      (node (ref "D4") (pin "AC3") (pinfunction "GND_AC3") (pintype "power_in"))
      (node (ref "D4") (pin "AC4") (pinfunction "GND_AC4") (pintype "power_in"))
      (node (ref "D4") (pin "AC6") (pinfunction "GND_AC6") (pintype "power_in"))
      (node (ref "D4") (pin "AD1") (pinfunction "GND_AD1") (pintype "power_in"))
      (node (ref "D4") (pin "AD16") (pinfunction "GND_AD16") (pintype "power_in"))
      (node (ref "D4") (pin "AD2") (pinfunction "GND_AD2") (pintype "power_in"))
      (node (ref "D4") (pin "AD26") (pinfunction "GND_AD26") (pintype "power_in"))
      (node (ref "D4") (pin "AD5") (pinfunction "GND_AD5") (pintype "power_in"))
      (node (ref "D4") (pin "AD7") (pinfunction "GND_AD7") (pintype "power_in"))
      (node (ref "D4") (pin "AE1") (pinfunction "GND_AE1") (pintype "power_in"))
      (node (ref "D4") (pin "AE19") (pinfunction "GND_AE19") (pintype "power_in"))
      (node (ref "D4") (pin "AE2") (pinfunction "GND_AE2") (pintype "power_in"))
      (node (ref "D4") (pin "AE29") (pinfunction "GND_AE29") (pintype "power_in"))
      (node (ref "D4") (pin "AE3") (pinfunction "GND_AE3") (pintype "power_in"))
      (node (ref "D4") (pin "AE4") (pinfunction "GND_AE4") (pintype "power_in"))
      (node (ref "D4") (pin "AE6") (pinfunction "GND_AE6") (pintype "power_in"))
      (node (ref "D4") (pin "AE8") (pinfunction "VREFB3AN0_AE8") (pintype "power_in"))
      (node (ref "D4") (pin "AE9") (pinfunction "GND_AE9") (pintype "power_in"))
      (node (ref "D4") (pin "AF1") (pinfunction "GND_AF1") (pintype "power_in"))
      (node (ref "D4") (pin "AF12") (pinfunction "GND_AF12") (pintype "power_in"))
      (node (ref "D4") (pin "AF2") (pinfunction "GND_AF2") (pintype "power_in"))
      (node (ref "D4") (pin "AF22") (pinfunction "GND_AF22") (pintype "power_in"))
      (node (ref "D4") (pin "AF5") (pinfunction "GND_AF5") (pintype "power_in"))
      (node (ref "D4") (pin "AG1") (pinfunction "GND_AG1") (pintype "power_in"))
      (node (ref "D4") (pin "AG15") (pinfunction "GND_AG15") (pintype "power_in"))
      (node (ref "D4") (pin "AG2") (pinfunction "GND_AG2") (pintype "power_in"))
      (node (ref "D4") (pin "AG25") (pinfunction "GND_AG25") (pintype "power_in"))
      (node (ref "D4") (pin "AG3") (pinfunction "GND_AG3") (pintype "power_in"))
      (node (ref "D4") (pin "AG4") (pinfunction "GND_AG4") (pintype "power_in"))
      (node (ref "D4") (pin "AH1") (pinfunction "GND_AH1") (pintype "power_in"))
      (node (ref "D4") (pin "AH18") (pinfunction "GND_AH18") (pintype "power_in"))
      (node (ref "D4") (pin "AH2") (pinfunction "GND_AH2") (pintype "power_in"))
      (node (ref "D4") (pin "AH28") (pinfunction "GND_AH28") (pintype "power_in"))
      (node (ref "D4") (pin "AH3") (pinfunction "GND_AH3") (pintype "power_in"))
      (node (ref "D4") (pin "AH8") (pinfunction "GND_AH8") (pintype "power_in"))
      (node (ref "D4") (pin "AJ11") (pinfunction "GND_AJ11") (pintype "power_in"))
      (node (ref "D4") (pin "AJ21") (pinfunction "GND_AJ21") (pintype "power_in"))
      (node (ref "D4") (pin "AJ6") (pinfunction "GND_AJ6") (pintype "power_in"))
      (node (ref "D4") (pin "AK14") (pinfunction "GND_AK14") (pintype "power_in"))
      (node (ref "D4") (pin "AK2") (pinfunction "GND_AK2") (pintype "power_in"))
      (node (ref "D4") (pin "AK24") (pinfunction "GND_AK24") (pintype "power_in"))
      (node (ref "D4") (pin "AK29") (pinfunction "GND_AK29") (pintype "power_in"))
      (node (ref "D4") (pin "B1") (pinfunction "GND_B1") (pintype "power_in"))
      (node (ref "D4") (pin "B10") (pinfunction "GND_B10") (pintype "power_in"))
      (node (ref "D4") (pin "B2") (pinfunction "GND_B2") (pintype "power_in"))
      (node (ref "D4") (pin "B20") (pinfunction "GND_B20") (pintype "power_in"))
      (node (ref "D4") (pin "B30") (pinfunction "GND_B30") (pintype "power_in"))
      (node (ref "D4") (pin "C13") (pinfunction "GND_C13") (pintype "power_in"))
      (node (ref "D4") (pin "C2") (pinfunction "GND_C2") (pintype "power_in"))
      (node (ref "D4") (pin "C23") (pinfunction "GND_C23") (pintype "power_in"))
      (node (ref "D4") (pin "C3") (pinfunction "GND_C3") (pintype "power_in"))
      (node (ref "D4") (pin "C4") (pinfunction "GND_C4") (pintype "power_in"))
      (node (ref "D4") (pin "D1") (pinfunction "GND_D1") (pintype "power_in"))
      (node (ref "D4") (pin "D16") (pinfunction "GND_D16") (pintype "power_in"))
      (node (ref "D4") (pin "D2") (pinfunction "GND_D2") (pintype "power_in"))
      (node (ref "D4") (pin "D26") (pinfunction "GND_D26") (pintype "power_in"))
      (node (ref "D4") (pin "D5") (pinfunction "GND_D5") (pintype "power_in"))
      (node (ref "D4") (pin "E19") (pinfunction "GND_E19") (pintype "power_in"))
      (node (ref "D4") (pin "E29") (pinfunction "GND_E29") (pintype "power_in"))
      (node (ref "D4") (pin "E3") (pinfunction "GND_E3") (pintype "power_in"))
      (node (ref "D4") (pin "E4") (pinfunction "GND_E4") (pintype "power_in"))
      (node (ref "D4") (pin "E5") (pinfunction "GND_E5") (pintype "power_in"))
      (node (ref "D4") (pin "E9") (pinfunction "GND_E9") (pintype "power_in"))
      (node (ref "D4") (pin "F1") (pinfunction "GND_F1") (pintype "power_in"))
      (node (ref "D4") (pin "F12") (pinfunction "GND_F12") (pintype "power_in"))
      (node (ref "D4") (pin "F2") (pinfunction "GND_F2") (pintype "power_in"))
      (node (ref "D4") (pin "F22") (pinfunction "GND_F22") (pintype "power_in"))
      (node (ref "D4") (pin "F5") (pinfunction "GND_F5") (pintype "power_in"))
      (node (ref "D4") (pin "G15") (pinfunction "GND_G15") (pintype "power_in"))
      (node (ref "D4") (pin "G24") (pinfunction "GND_G24") (pintype "power_in"))
      (node (ref "D4") (pin "G25") (pinfunction "GND_G25") (pintype "power_in"))
      (node (ref "D4") (pin "G3") (pinfunction "GND_G3") (pintype "power_in"))
      (node (ref "D4") (pin "G4") (pinfunction "GND_G4") (pintype "power_in"))
      (node (ref "D4") (pin "G5") (pinfunction "MSEL2_G5") (pintype "input"))
      (node (ref "D4") (pin "H1") (pinfunction "GND_H1") (pintype "power_in"))
      (node (ref "D4") (pin "H11") (pinfunction "GND_H11") (pintype "power_in"))
      (node (ref "D4") (pin "H18") (pinfunction "GND_H18") (pintype "power_in"))
      (node (ref "D4") (pin "H2") (pinfunction "GND_H2") (pintype "power_in"))
      (node (ref "D4") (pin "H28") (pinfunction "GND_H28") (pintype "power_in"))
      (node (ref "D4") (pin "H5") (pinfunction "GND_H5") (pintype "power_in"))
      (node (ref "D4") (pin "H6") (pinfunction "nCE_H6") (pintype "input"))
      (node (ref "D4") (pin "H8") (pinfunction "GND_H8") (pintype "power_in"))
      (node (ref "D4") (pin "J11") (pinfunction "GND_J11") (pintype "power_in"))
      (node (ref "D4") (pin "J21") (pinfunction "GND_J21") (pintype "power_in"))
      (node (ref "D4") (pin "J3") (pinfunction "GND_J3") (pintype "power_in"))
      (node (ref "D4") (pin "J4") (pinfunction "GND_J4") (pintype "power_in"))
      (node (ref "D4") (pin "J6") (pinfunction "GND_J6") (pintype "power_in"))
      (node (ref "D4") (pin "K1") (pinfunction "GND_K1") (pintype "power_in"))
      (node (ref "D4") (pin "K14") (pinfunction "GND_K14") (pintype "power_in"))
      (node (ref "D4") (pin "K2") (pinfunction "GND_K2") (pintype "power_in"))
      (node (ref "D4") (pin "K24") (pinfunction "GND_K24") (pintype "power_in"))
      (node (ref "D4") (pin "K5") (pinfunction "GND_K5") (pintype "power_in"))
      (node (ref "D4") (pin "K9") (pinfunction "GND_K9") (pintype "power_in"))
      (node (ref "D4") (pin "L1") (pinfunction "GND_L1") (pintype "power_in"))
      (node (ref "D4") (pin "L17") (pinfunction "GND_L17") (pintype "power_in"))
      (node (ref "D4") (pin "L2") (pinfunction "GND_L2") (pintype "power_in"))
      (node (ref "D4") (pin "L27") (pinfunction "GND_L27") (pintype "power_in"))
      (node (ref "D4") (pin "L3") (pinfunction "GND_L3") (pintype "power_in"))
      (node (ref "D4") (pin "L4") (pinfunction "GND_L4") (pintype "power_in"))
      (node (ref "D4") (pin "L6") (pinfunction "GND_L6") (pintype "power_in"))
      (node (ref "D4") (pin "M1") (pinfunction "GND_M1") (pintype "power_in"))
      (node (ref "D4") (pin "M10") (pinfunction "GND_M10") (pintype "power_in"))
      (node (ref "D4") (pin "M14") (pinfunction "GND_M14") (pintype "power_in"))
      (node (ref "D4") (pin "M16") (pinfunction "GND_M16") (pintype "power_in"))
      (node (ref "D4") (pin "M18") (pinfunction "GND_M18") (pintype "power_in"))
      (node (ref "D4") (pin "M2") (pinfunction "GND_M2") (pintype "power_in"))
      (node (ref "D4") (pin "M20") (pinfunction "GND_M20") (pintype "power_in"))
      (node (ref "D4") (pin "M26") (pinfunction "VREFB6AN0_M26") (pintype "power_in"))
      (node (ref "D4") (pin "M30") (pinfunction "GND_M30") (pintype "power_in"))
      (node (ref "D4") (pin "M5") (pinfunction "GND_M5") (pintype "power_in"))
      (node (ref "D4") (pin "N1") (pinfunction "GND_N1") (pintype "power_in"))
      (node (ref "D4") (pin "N13") (pinfunction "GND_N13") (pintype "power_in"))
      (node (ref "D4") (pin "N15") (pinfunction "GND_N15") (pintype "power_in"))
      (node (ref "D4") (pin "N17") (pinfunction "GND_N17") (pintype "power_in"))
      (node (ref "D4") (pin "N19") (pinfunction "GND_N19") (pintype "power_in"))
      (node (ref "D4") (pin "N2") (pinfunction "GND_N2") (pintype "power_in"))
      (node (ref "D4") (pin "N23") (pinfunction "GND_N23") (pintype "power_in"))
      (node (ref "D4") (pin "N3") (pinfunction "GND_N3") (pintype "power_in"))
      (node (ref "D4") (pin "N4") (pinfunction "GND_N4") (pintype "power_in"))
      (node (ref "D4") (pin "N6") (pinfunction "GND_N6") (pintype "power_in"))
      (node (ref "D4") (pin "N7") (pinfunction "GND_N7") (pintype "power_in"))
      (node (ref "D4") (pin "N8") (pinfunction "GND_N8") (pintype "power_in"))
      (node (ref "D4") (pin "P1") (pinfunction "GND_P1") (pintype "power_in"))
      (node (ref "D4") (pin "P11") (pinfunction "GND_P11") (pintype "power_in"))
      (node (ref "D4") (pin "P14") (pinfunction "GND_P14") (pintype "power_in"))
      (node (ref "D4") (pin "P16") (pinfunction "GND_P16") (pintype "power_in"))
      (node (ref "D4") (pin "P18") (pinfunction "GND_P18") (pintype "power_in"))
      (node (ref "D4") (pin "P2") (pinfunction "GND_P2") (pintype "power_in"))
      (node (ref "D4") (pin "P26") (pinfunction "GND_P26") (pintype "power_in"))
      (node (ref "D4") (pin "P27") (pinfunction "VREFB5BN0_P27") (pintype "power_in"))
      (node (ref "D4") (pin "P5") (pinfunction "GND_P5") (pintype "power_in"))
      (node (ref "D4") (pin "P7") (pinfunction "MSEL3_P7") (pintype "input"))
      (node (ref "D4") (pin "P8") (pinfunction "GND_P8") (pintype "power_in"))
      (node (ref "D4") (pin "R1") (pinfunction "GND_R1") (pintype "power_in"))
      (node (ref "D4") (pin "R13") (pinfunction "GND_R13") (pintype "power_in"))
      (node (ref "D4") (pin "R15") (pinfunction "GND_R15") (pintype "power_in"))
      (node (ref "D4") (pin "R17") (pinfunction "GND_R17") (pintype "power_in"))
      (node (ref "D4") (pin "R19") (pinfunction "GND_R19") (pintype "power_in"))
      (node (ref "D4") (pin "R2") (pinfunction "GND_R2") (pintype "power_in"))
      (node (ref "D4") (pin "R29") (pinfunction "GND_R29") (pintype "power_in"))
      (node (ref "D4") (pin "R3") (pinfunction "GND_R3") (pintype "power_in"))
      (node (ref "D4") (pin "R4") (pinfunction "GND_R4") (pintype "power_in"))
      (node (ref "D4") (pin "R6") (pinfunction "GND_R6") (pintype "power_in"))
      (node (ref "D4") (pin "R7") (pinfunction "GND_R7") (pintype "power_in"))
      (node (ref "D4") (pin "R8") (pinfunction "GND_R8") (pintype "power_in"))
      (node (ref "D4") (pin "R9") (pinfunction "GND_R9") (pintype "power_in"))
      (node (ref "D4") (pin "T1") (pinfunction "GND_T1") (pintype "power_in"))
      (node (ref "D4") (pin "T12") (pinfunction "GND_T12") (pintype "power_in"))
      (node (ref "D4") (pin "T14") (pinfunction "GND_T14") (pintype "power_in"))
      (node (ref "D4") (pin "T16") (pinfunction "GND_T16") (pintype "power_in"))
      (node (ref "D4") (pin "T18") (pinfunction "GND_T18") (pintype "power_in"))
      (node (ref "D4") (pin "T2") (pinfunction "GND_T2") (pintype "power_in"))
      (node (ref "D4") (pin "T20") (pinfunction "GND_T20") (pintype "power_in"))
      (node (ref "D4") (pin "T22") (pinfunction "GND_T22") (pintype "power_in"))
      (node (ref "D4") (pin "T5") (pinfunction "GND_T5") (pintype "power_in"))
      (node (ref "D4") (pin "T8") (pinfunction "MSEL0_T8") (pintype "input"))
      (node (ref "D4") (pin "U1") (pinfunction "GND_U1") (pintype "power_in"))
      (node (ref "D4") (pin "U13") (pinfunction "GND_U13") (pintype "power_in"))
      (node (ref "D4") (pin "U15") (pinfunction "GND_U15") (pintype "power_in"))
      (node (ref "D4") (pin "U17") (pinfunction "GND_U17") (pintype "power_in"))
      (node (ref "D4") (pin "U19") (pinfunction "GND_U19") (pintype "power_in"))
      (node (ref "D4") (pin "U2") (pinfunction "GND_U2") (pintype "power_in"))
      (node (ref "D4") (pin "U25") (pinfunction "GND_U25") (pintype "power_in"))
      (node (ref "D4") (pin "U3") (pinfunction "GND_U3") (pintype "power_in"))
      (node (ref "D4") (pin "U4") (pinfunction "GND_U4") (pintype "power_in"))
      (node (ref "D4") (pin "U6") (pinfunction "GND_U6") (pintype "power_in"))
      (node (ref "D4") (pin "V1") (pinfunction "GND_V1") (pintype "power_in"))
      (node (ref "D4") (pin "V14") (pinfunction "GND_V14") (pintype "power_in"))
      (node (ref "D4") (pin "V16") (pinfunction "GND_V16") (pintype "power_in"))
      (node (ref "D4") (pin "V18") (pinfunction "GND_V18") (pintype "power_in"))
      (node (ref "D4") (pin "V2") (pinfunction "GND_V2") (pintype "power_in"))
      (node (ref "D4") (pin "V20") (pinfunction "GND_V20") (pintype "power_in"))
      (node (ref "D4") (pin "V23") (pinfunction "GND_V23") (pintype "power_in"))
      (node (ref "D4") (pin "V28") (pinfunction "GND_V28") (pintype "power_in"))
      (node (ref "D4") (pin "V5") (pinfunction "GND_V5") (pintype "power_in"))
      (node (ref "D4") (pin "V8") (pinfunction "GND_V8") (pintype "power_in"))
      (node (ref "D4") (pin "W1") (pinfunction "GND_W1") (pintype "power_in"))
      (node (ref "D4") (pin "W11") (pinfunction "GND_W11") (pintype "power_in"))
      (node (ref "D4") (pin "W13") (pinfunction "GND_W13") (pintype "power_in"))
      (node (ref "D4") (pin "W15") (pinfunction "GND_W15") (pintype "power_in"))
      (node (ref "D4") (pin "W17") (pinfunction "GND_W17") (pintype "power_in"))
      (node (ref "D4") (pin "W19") (pinfunction "GND_W19") (pintype "power_in"))
      (node (ref "D4") (pin "W2") (pinfunction "GND_W2") (pintype "power_in"))
      (node (ref "D4") (pin "W21") (pinfunction "GND_W21") (pintype "power_in"))
      (node (ref "D4") (pin "W3") (pinfunction "GND_W3") (pintype "power_in"))
      (node (ref "D4") (pin "W4") (pinfunction "GND_W4") (pintype "power_in"))
      (node (ref "D4") (pin "W6") (pinfunction "GND_W6") (pintype "power_in"))
      (node (ref "D4") (pin "W7") (pinfunction "GND_W7") (pintype "power_in"))
      (node (ref "D4") (pin "W8") (pinfunction "GND_W8") (pintype "power_in"))
      (node (ref "D4") (pin "Y1") (pinfunction "GND_Y1") (pintype "power_in"))
      (node (ref "D4") (pin "Y14") (pinfunction "GND_Y14") (pintype "power_in"))
      (node (ref "D4") (pin "Y2") (pinfunction "GND_Y2") (pintype "power_in"))
      (node (ref "D4") (pin "Y24") (pinfunction "GND_Y24") (pintype "power_in"))
      (node (ref "D4") (pin "Y5") (pinfunction "GND_Y5") (pintype "power_in"))
      (node (ref "D4") (pin "Y7") (pinfunction "GND_Y7") (pintype "power_in"))
      (node (ref "R33") (pin "1") (pinfunction "1_1") (pintype "passive"))
      (node (ref "X1") (pin "10") (pintype "passive"))
      (node (ref "X1") (pin "2") (pintype "passive"))
    )
    (net (code "2") (name "/Fpga_CONF_DONE") (class "Default")
      (node (ref "D4") (pin "L8") (pinfunction "CONF_DONE_L8") (pintype "bidirectional"))
      (node (ref "R31") (pin "2") (pinfunction "2_2") (pintype "passive"))
    )
    (net (code "3") (name "/Fpga_DCLK") (class "Default")
      (node (ref "D4") (pin "T7") (pinfunction "DCLK_T7") (pintype "bidirectional"))
      (node (ref "R32") (pin "2") (pinfunction "2_2") (pintype "passive"))
    )
    (net (code "4") (name "/Fpga_Data0") (class "Default")
      (node (ref "D4") (pin "AG5") (pinfunction "AS_DATA0,_ASDO,_DATA0_AG5") (pintype "bidirectional"))
    )
    (net (code "5") (name "/Fpga_nCONFIG") (class "Default")
      (node (ref "D4") (pin "C5") (pinfunction "nCONFIG_C5") (pintype "input"))
      (node (ref "R30") (pin "2") (pinfunction "2_2") (pintype "passive"))
    )
    (net (code "6") (name "/Fpga_nSTATUS") (class "Default")
      (node (ref "D4") (pin "K7") (pinfunction "nSTATUS_K7") (pintype "bidirectional"))
    )
    (net (code "7") (name "/TCK") (class "Default")
      (node (ref "D4") (pin "AC7") (pinfunction "TCK_AC7") (pintype "input"))
      (node (ref "R26") (pin "2") (pinfunction "2_2") (pintype "passive"))
      (node (ref "R33") (pin "2") (pinfunction "2_2") (pintype "passive"))
      (node (ref "X1") (pin "1") (pintype "passive"))
    )
    (net (code "8") (name "/TDI") (class "Default")
      (node (ref "D4") (pin "U7") (pinfunction "TDI_U7") (pintype "input"))
      (node (ref "R27") (pin "1") (pinfunction "1_1") (pintype "passive"))
      (node (ref "X1") (pin "9") (pintype "passive"))
    )
    (net (code "9") (name "/TDO") (class "Default")
      (node (ref "D4") (pin "W9") (pinfunction "TDO_W9") (pintype "output"))
      (node (ref "X1") (pin "3") (pintype "passive"))
    )
    (net (code "10") (name "/TMS") (class "Default")
      (node (ref "D4") (pin "V7") (pinfunction "TMS_V7") (pintype "input"))
      (node (ref "R25") (pin "2") (pinfunction "2_2") (pintype "passive"))
      (node (ref "X1") (pin "5") (pintype "passive"))
    )
    (net (code "11") (name "/v1p1d") (class "Default")
      (node (ref "C63") (pin "2") (pinfunction "2_2") (pintype "passive"))
      (node (ref "C64") (pin "2") (pinfunction "2_2") (pintype "passive"))
      (node (ref "C65") (pin "2") (pinfunction "2_2") (pintype "passive"))
      (node (ref "C66") (pin "2") (pinfunction "2_2") (pintype "passive"))
      (node (ref "C67") (pin "2") (pinfunction "2_2") (pintype "passive"))
      (node (ref "C68") (pin "2") (pinfunction "2_2") (pintype "passive"))
      (node (ref "C69") (pin "2") (pinfunction "2_2") (pintype "passive"))
      (node (ref "C75") (pin "2") (pinfunction "2_2") (pintype "passive"))
      (node (ref "C76") (pin "2") (pinfunction "2_2") (pintype "passive"))
      (node (ref "C77") (pin "2") (pinfunction "2_2") (pintype "passive"))
      (node (ref "C78") (pin "2") (pinfunction "2_2") (pintype "passive"))
      (node (ref "C79") (pin "2") (pinfunction "2_2") (pintype "passive"))
      (node (ref "C80") (pin "2") (pinfunction "2_2") (pintype "passive"))
      (node (ref "C81") (pin "2") (pinfunction "2_2") (pintype "passive"))
      (node (ref "C87") (pin "2") (pinfunction "2_2") (pintype "passive"))
      (node (ref "C88") (pin "2") (pinfunction "2_2") (pintype "passive"))
      (node (ref "C89") (pin "2") (pinfunction "2_2") (pintype "passive"))
      (node (ref "C90") (pin "2") (pinfunction "2_2") (pintype "passive"))
      (node (ref "C91") (pin "2") (pinfunction "2_2") (pintype "passive"))
      (node (ref "C92") (pin "2") (pinfunction "2_2") (pintype "passive"))
      (node (ref "C93") (pin "2") (pinfunction "2_2") (pintype "passive"))
      (node (ref "C94") (pin "2") (pinfunction "2_2") (pintype "passive"))
      (node (ref "D4") (pin "AA5") (pinfunction "VCC_AA5") (pintype "power_in"))
      (node (ref "D4") (pin "AC5") (pinfunction "VCC_AC5") (pintype "power_in"))
      (node (ref "D4") (pin "AD6") (pinfunction "VCC_AD6") (pintype "power_in"))
      (node (ref "D4") (pin "J5") (pinfunction "VCC_J5") (pintype "power_in"))
      (node (ref "D4") (pin "L5") (pinfunction "VCC_L5") (pintype "power_in"))
      (node (ref "D4") (pin "M13") (pinfunction "VCC_M13") (pintype "power_in"))
      (node (ref "D4") (pin "M15") (pinfunction "VCC_M15") (pintype "power_in"))
      (node (ref "D4") (pin "M17") (pinfunction "VCC_M17") (pintype "power_in"))
      (node (ref "D4") (pin "M19") (pinfunction "VCC_M19") (pintype "power_in"))
      (node (ref "D4") (pin "M6") (pinfunction "VCC_M6") (pintype "power_in"))
      (node (ref "D4") (pin "N14") (pinfunction "VCC_N14") (pintype "power_in"))
      (node (ref "D4") (pin "N16") (pinfunction "VCC_N16") (pintype "power_in"))
      (node (ref "D4") (pin "N18") (pinfunction "VCC_N18") (pintype "power_in"))
      (node (ref "D4") (pin "N5") (pinfunction "VCC_N5") (pintype "power_in"))
      (node (ref "D4") (pin "P13") (pinfunction "VCC_P13") (pintype "power_in"))
      (node (ref "D4") (pin "P15") (pinfunction "VCC_P15") (pintype "power_in"))
      (node (ref "D4") (pin "P17") (pinfunction "VCC_P17") (pintype "power_in"))
      (node (ref "D4") (pin "P19") (pinfunction "VCC_P19") (pintype "power_in"))
      (node (ref "D4") (pin "R14") (pinfunction "VCC_R14") (pintype "power_in"))
      (node (ref "D4") (pin "R16") (pinfunction "VCC_R16") (pintype "power_in"))
      (node (ref "D4") (pin "R18") (pinfunction "VCC_R18") (pintype "power_in"))
      (node (ref "D4") (pin "R5") (pinfunction "VCC_R5") (pintype "power_in"))
      (node (ref "D4") (pin "T13") (pinfunction "VCC_T13") (pintype "power_in"))
      (node (ref "D4") (pin "T15") (pinfunction "VCC_T15") (pintype "power_in"))
      (node (ref "D4") (pin "T17") (pinfunction "VCC_T17") (pintype "power_in"))
      (node (ref "D4") (pin "T19") (pinfunction "VCC_T19") (pintype "power_in"))
      (node (ref "D4") (pin "T6") (pinfunction "VCC_T6") (pintype "power_in"))
      (node (ref "D4") (pin "U14") (pinfunction "VCC_U14") (pintype "power_in"))
      (node (ref "D4") (pin "U16") (pinfunction "VCC_U16") (pintype "power_in"))
      (node (ref "D4") (pin "U18") (pinfunction "VCC_U18") (pintype "power_in"))
      (node (ref "D4") (pin "U20") (pinfunction "VCC_U20") (pintype "power_in"))
      (node (ref "D4") (pin "U5") (pinfunction "VCC_U5") (pintype "power_in"))
      (node (ref "D4") (pin "V13") (pinfunction "VCC_V13") (pintype "power_in"))
      (node (ref "D4") (pin "V15") (pinfunction "VCC_V15") (pintype "power_in"))
      (node (ref "D4") (pin "V17") (pinfunction "VCC_V17") (pintype "power_in"))
      (node (ref "D4") (pin "V19") (pinfunction "VCC_V19") (pintype "power_in"))
      (node (ref "D4") (pin "W14") (pinfunction "VCC_W14") (pintype "power_in"))
      (node (ref "D4") (pin "W16") (pinfunction "VCC_W16") (pintype "power_in"))
      (node (ref "D4") (pin "W18") (pinfunction "VCC_W18") (pintype "power_in"))
      (node (ref "D4") (pin "W20") (pinfunction "VCC_W20") (pintype "power_in"))
      (node (ref "D4") (pin "W5") (pinfunction "VCC_W5") (pintype "power_in"))
      (node (ref "D4") (pin "Y6") (pinfunction "VCC_Y6") (pintype "power_in"))
    )
    (net (code "12") (name "/v1p5d") (class "Default")
      (node (ref "C111") (pin "2") (pinfunction "2_2") (pintype "passive"))
      (node (ref "C112") (pin "2") (pinfunction "2_2") (pintype "passive"))
      (node (ref "C113") (pin "2") (pinfunction "2_2") (pintype "passive"))
      (node (ref "C114") (pin "2") (pinfunction "2_2") (pintype "passive"))
      (node (ref "C115") (pin "2") (pinfunction "2_2") (pintype "passive"))
      (node (ref "C116") (pin "2") (pinfunction "2_2") (pintype "passive"))
      (node (ref "C117") (pin "2") (pinfunction "2_2") (pintype "passive"))
      (node (ref "C124") (pin "2") (pinfunction "2_2") (pintype "passive"))
      (node (ref "C125") (pin "2") (pinfunction "2_2") (pintype "passive"))
      (node (ref "C126") (pin "2") (pinfunction "2_2") (pintype "passive"))
      (node (ref "C127") (pin "2") (pinfunction "2_2") (pintype "passive"))
      (node (ref "C128") (pin "2") (pinfunction "2_2") (pintype "passive"))
      (node (ref "C129") (pin "2") (pinfunction "2_2") (pintype "passive"))
      (node (ref "C130") (pin "2") (pinfunction "2_2") (pintype "passive"))
      (node (ref "C135") (pin "2") (pinfunction "2_2") (pintype "passive"))
      (node (ref "C136") (pin "2") (pinfunction "2_2") (pintype "passive"))
      (node (ref "C137") (pin "2") (pinfunction "2_2") (pintype "passive"))
      (node (ref "C138") (pin "2") (pinfunction "2_2") (pintype "passive"))
      (node (ref "C250") (pin "2") (pinfunction "2_2") (pintype "passive"))
      (node (ref "C251") (pin "2") (pinfunction "2_2") (pintype "passive"))
      (node (ref "C252") (pin "2") (pinfunction "2_2") (pintype "passive"))
      (node (ref "C253") (pin "2") (pinfunction "2_2") (pintype "passive"))
      (node (ref "D4") (pin "A22") (pinfunction "VCCIO7A_A22") (pintype "power_in"))
      (node (ref "D4") (pin "A7") (pinfunction "VCCIO8A_A7") (pintype "power_in"))
      (node (ref "D4") (pin "AA12") (pinfunction "VCCIO3B_AA12") (pintype "power_in"))
      (node (ref "D4") (pin "AB15") (pinfunction "VCCIO4A_AB15") (pintype "power_in"))
      (node (ref "D4") (pin "AC18") (pinfunction "VCCIO4A_AC18") (pintype "power_in"))
      (node (ref "D4") (pin "AD21") (pinfunction "VCCIO4A_AD21") (pintype "power_in"))
      (node (ref "D4") (pin "AE14") (pinfunction "VCCIO3B_AE14") (pintype "power_in"))
      (node (ref "D4") (pin "AF17") (pinfunction "VCCIO4A_AF17") (pintype "power_in"))
      (node (ref "D4") (pin "AG10") (pinfunction "VCCIO3B_AG10") (pintype "power_in"))
      (node (ref "D4") (pin "AG20") (pinfunction "VCCIO4A_AG20") (pintype "power_in"))
      (node (ref "D4") (pin "AH13") (pinfunction "VCCIO3B_AH13") (pintype "power_in"))
      (node (ref "D4") (pin "AH23") (pinfunction "VCCIO4A_AH23") (pintype "power_in"))
      (node (ref "D4") (pin "AJ16") (pinfunction "VCCIO4A_AJ16") (pintype "power_in"))
      (node (ref "D4") (pin "AJ26") (pinfunction "VCCIO4A_AJ26") (pintype "power_in"))
      (node (ref "D4") (pin "AK19") (pinfunction "VCCIO4A_AK19") (pintype "power_in"))
      (node (ref "D4") (pin "AK4") (pinfunction "VCCIO3B_AK4") (pintype "power_in"))
      (node (ref "D4") (pin "AK9") (pinfunction "VCCIO3B_AK9") (pintype "power_in"))
      (node (ref "D4") (pin "B15") (pinfunction "VCCIO7A_B15") (pintype "power_in"))
      (node (ref "D4") (pin "B25") (pinfunction "VCCIO7A_B25") (pintype "power_in"))
      (node (ref "D4") (pin "B5") (pinfunction "VCCIO8A_B5") (pintype "power_in"))
      (node (ref "D4") (pin "C18") (pinfunction "VCCIO7A_C18") (pintype "power_in"))
      (node (ref "D4") (pin "C8") (pinfunction "VCCIO8A_C8") (pintype "power_in"))
      (node (ref "D4") (pin "D11") (pinfunction "VCCIO8A_D11") (pintype "power_in"))
      (node (ref "D4") (pin "D21") (pinfunction "VCCIO7A_D21") (pintype "power_in"))
      (node (ref "D4") (pin "E14") (pinfunction "VCCIO8A_E14") (pintype "power_in"))
      (node (ref "D4") (pin "E24") (pinfunction "VCCIO7A_E24") (pintype "power_in"))
      (node (ref "D4") (pin "F17") (pinfunction "VCCIO7A_F17") (pintype "power_in"))
      (node (ref "D4") (pin "F7") (pinfunction "VCCIO8A_F7") (pintype "power_in"))
      (node (ref "D4") (pin "G10") (pinfunction "VCCIO8A_G10") (pintype "power_in"))
      (node (ref "D4") (pin "G20") (pinfunction "VCCIO7A_G20") (pintype "power_in"))
      (node (ref "D4") (pin "H10") (pinfunction "VCCBAT_H10") (pintype "power_in"))
      (node (ref "D4") (pin "H13") (pinfunction "VCCIO8A_H13") (pintype "power_in"))
      (node (ref "D4") (pin "H23") (pinfunction "VCCIO7A_H23") (pintype "power_in"))
      (node (ref "D4") (pin "J16") (pinfunction "VCCIO8A_J16") (pintype "power_in"))
      (node (ref "D4") (pin "K19") (pinfunction "VCCIO7A_K19") (pintype "power_in"))
      (node (ref "D4") (pin "L12") (pinfunction "VCCIO8A_L12") (pintype "power_in"))
      (node (ref "D4") (pin "Y19") (pinfunction "VCCIO4A_Y19") (pintype "power_in"))
    )
    (net (code "13") (name "/v2p5d") (class "Default")
      (node (ref "C100") (pin "2") (pinfunction "2_2") (pintype "passive"))
      (node (ref "C101") (pin "2") (pinfunction "2_2") (pintype "passive"))
      (node (ref "C102") (pin "2") (pinfunction "2_2") (pintype "passive"))
      (node (ref "C103") (pin "2") (pinfunction "2_2") (pintype "passive"))
      (node (ref "C104") (pin "2") (pinfunction "2_2") (pintype "passive"))
      (node (ref "C105") (pin "2") (pinfunction "2_2") (pintype "passive"))
      (node (ref "C106") (pin "2") (pinfunction "2_2") (pintype "passive"))
      (node (ref "C107") (pin "2") (pinfunction "2_2") (pintype "passive"))
      (node (ref "C108") (pin "2") (pinfunction "2_2") (pintype "passive"))
      (node (ref "C122") (pin "2") (pinfunction "2_2") (pintype "passive"))
      (node (ref "C123") (pin "2") (pinfunction "2_2") (pintype "passive"))
      (node (ref "C131") (pin "2") (pinfunction "2_2") (pintype "passive"))
      (node (ref "C132") (pin "2") (pinfunction "2_2") (pintype "passive"))
      (node (ref "C133") (pin "2") (pinfunction "2_2") (pintype "passive"))
      (node (ref "C134") (pin "2") (pinfunction "2_2") (pintype "passive"))
      (node (ref "C139") (pin "2") (pinfunction "2_2") (pintype "passive"))
      (node (ref "C140") (pin "2") (pinfunction "2_2") (pintype "passive"))
      (node (ref "C141") (pin "2") (pinfunction "2_2") (pintype "passive"))
      (node (ref "C142") (pin "2") (pinfunction "2_2") (pintype "passive"))
      (node (ref "C97") (pin "2") (pinfunction "2_2") (pintype "passive"))
      (node (ref "C98") (pin "2") (pinfunction "2_2") (pintype "passive"))
      (node (ref "C99") (pin "2") (pinfunction "2_2") (pintype "passive"))
      (node (ref "D4") (pin "AA22") (pinfunction "VCCIO5A_AA22") (pintype "power_in"))
      (node (ref "D4") (pin "AB11") (pinfunction "VCCPD3A_AB11") (pintype "power_in"))
      (node (ref "D4") (pin "AB25") (pinfunction "VCCIO5A_AB25") (pintype "power_in"))
      (node (ref "D4") (pin "AC12") (pinfunction "VCCPD3B4A_AC12") (pintype "power_in"))
      (node (ref "D4") (pin "AC17") (pinfunction "VCCPD3B4A_AC17") (pintype "power_in"))
      (node (ref "D4") (pin "AC20") (pinfunction "VCCPD3B4A_AC20") (pintype "power_in"))
      (node (ref "D4") (pin "AC28") (pinfunction "VCCIO5B_AC28") (pintype "power_in"))
      (node (ref "D4") (pin "AD10") (pinfunction "VCCPD3A_AD10") (pintype "power_in"))
      (node (ref "D4") (pin "AD15") (pinfunction "VCCPD3B4A_AD15") (pintype "power_in"))
      (node (ref "D4") (pin "AE11") (pinfunction "VCCPD3B4A_AE11") (pintype "power_in"))
      (node (ref "D4") (pin "AE21") (pinfunction "VCCPD3B4A_AE21") (pintype "power_in"))
      (node (ref "D4") (pin "AE24") (pinfunction "VCCIO5A_AE24") (pintype "power_in"))
      (node (ref "D4") (pin "AF27") (pinfunction "VCCIO5A_AF27") (pintype "power_in"))
      (node (ref "D4") (pin "AG30") (pinfunction "VCCIO5B_AG30") (pintype "power_in"))
      (node (ref "D4") (pin "C28") (pinfunction "VCCIO6A_C28") (pintype "power_in"))
      (node (ref "D4") (pin "D24") (pinfunction "VCCPD7A8A_D24") (pintype "power_in"))
      (node (ref "D4") (pin "F11") (pinfunction "VCCPD7A8A_F11") (pintype "power_in"))
      (node (ref "D4") (pin "F21") (pinfunction "VCCPD7A8A_F21") (pintype "power_in"))
      (node (ref "D4") (pin "F23") (pinfunction "VCCPD7A8A_F23") (pintype "power_in"))
      (node (ref "D4") (pin "F27") (pinfunction "VCCIO6A_F27") (pintype "power_in"))
      (node (ref "D4") (pin "G13") (pinfunction "VCCPD7A8A_G13") (pintype "power_in"))
      (node (ref "D4") (pin "G16") (pinfunction "VCCPD7A8A_G16") (pintype "power_in"))
      (node (ref "D4") (pin "G19") (pinfunction "VCCPD7A8A_G19") (pintype "power_in"))
      (node (ref "D4") (pin "G30") (pinfunction "VCCIO6A_G30") (pintype "power_in"))
      (node (ref "D4") (pin "J26") (pinfunction "VCCIO6A_J26") (pintype "power_in"))
      (node (ref "D4") (pin "K23") (pinfunction "VCCPD6A_K23") (pintype "power_in"))
      (node (ref "D4") (pin "K29") (pinfunction "VCCIO6A_K29") (pintype "power_in"))
      (node (ref "D4") (pin "L22") (pinfunction "VCCIO6A_L22") (pintype "power_in"))
      (node (ref "D4") (pin "M24") (pinfunction "VCCPD6A_M24") (pintype "power_in"))
      (node (ref "D4") (pin "M25") (pinfunction "VCCIO6A_M25") (pintype "power_in"))
      (node (ref "D4") (pin "N28") (pinfunction "VCCIO6A_N28") (pintype "power_in"))
      (node (ref "D4") (pin "P21") (pinfunction "VCCIO6A_P21") (pintype "power_in"))
      (node (ref "D4") (pin "P24") (pinfunction "VCCPD6A_P24") (pintype "power_in"))
      (node (ref "D4") (pin "R24") (pinfunction "VCCIO6A_R24") (pintype "power_in"))
      (node (ref "D4") (pin "T26") (pinfunction "VCCPD5B_T26") (pintype "power_in"))
      (node (ref "D4") (pin "T27") (pinfunction "VCCIO5B_T27") (pintype "power_in"))
      (node (ref "D4") (pin "U24") (pinfunction "VCCPD5B_U24") (pintype "power_in"))
      (node (ref "D4") (pin "U30") (pinfunction "VCCIO5B_U30") (pintype "power_in"))
      (node (ref "D4") (pin "W23") (pinfunction "VCCPD5A_W23") (pintype "power_in"))
      (node (ref "D4") (pin "W25") (pinfunction "VCCPD5A_W25") (pintype "power_in"))
      (node (ref "D4") (pin "W26") (pinfunction "VCCIO5B_W26") (pintype "power_in"))
      (node (ref "D4") (pin "Y29") (pinfunction "VCCIO5B_Y29") (pintype "power_in"))
      (node (ref "L3") (pin "2") (pinfunction "2_2") (pintype "passive"))
      (node (ref "L4") (pin "2") (pinfunction "2_2") (pintype "passive"))
      (node (ref "L5") (pin "2") (pinfunction "2_2") (pintype "passive"))
    )
    (net (code "14") (name "/vRefDDR0") (class "Default")
      (node (ref "C118") (pin "2") (pinfunction "2_2") (pintype "passive"))
      (node (ref "C119") (pin "2") (pinfunction "2_2") (pintype "passive"))
      (node (ref "D4") (pin "AH16") (pinfunction "VREFB4AN0_AH16") (pintype "power_in"))
      (node (ref "D4") (pin "AJ13") (pinfunction "VREFB3BN0_AJ13") (pintype "power_in"))
    )
    (net (code "15") (name "/vRefDDR1") (class "Default")
      (node (ref "C120") (pin "2") (pinfunction "2_2") (pintype "passive"))
      (node (ref "C121") (pin "2") (pinfunction "2_2") (pintype "passive"))
      (node (ref "D4") (pin "B16") (pinfunction "VREFB7AN0_B16") (pintype "power_in"))
      (node (ref "D4") (pin "B9") (pinfunction "VREFB8AN0_B9") (pintype "power_in"))
    )
    (net (code "16") (name "/vcc_aux") (class "Default")
      (node (ref "C82") (pin "2") (pinfunction "2_2") (pintype "passive"))
      (node (ref "C83") (pin "2") (pinfunction "2_2") (pintype "passive"))
      (node (ref "C84") (pin "2") (pinfunction "2_2") (pintype "passive"))
      (node (ref "C85") (pin "2") (pinfunction "2_2") (pintype "passive"))
      (node (ref "C86") (pin "2") (pinfunction "2_2") (pintype "passive"))
      (node (ref "D4") (pin "AC10") (pinfunction "VCC_AUX_AC10") (pintype "power_in"))
      (node (ref "D4") (pin "AC16") (pinfunction "VCC_AUX_AC16") (pintype "power_in"))
      (node (ref "D4") (pin "AD22") (pinfunction "VCC_AUX_AD22") (pintype "power_in"))
      (node (ref "D4") (pin "G11") (pinfunction "VCC_AUX_G11") (pintype "power_in"))
      (node (ref "D4") (pin "H16") (pinfunction "VCC_AUX_H16") (pintype "power_in"))
      (node (ref "D4") (pin "H22") (pinfunction "VCC_AUX_H22") (pintype "power_in"))
      (node (ref "L4") (pin "1") (pinfunction "1_1") (pintype "passive"))
    )
    (net (code "17") (name "/vcc_pll") (class "Default")
      (node (ref "C70") (pin "2") (pinfunction "2_2") (pintype "passive"))
      (node (ref "C71") (pin "2") (pinfunction "2_2") (pintype "passive"))
      (node (ref "C72") (pin "2") (pinfunction "2_2") (pintype "passive"))
      (node (ref "C73") (pin "2") (pinfunction "2_2") (pintype "passive"))
      (node (ref "C74") (pin "2") (pinfunction "2_2") (pintype "passive"))
      (node (ref "D4") (pin "AB23") (pinfunction "VCCA_FPLL_AB23") (pintype "power_in"))
      (node (ref "D4") (pin "AB6") (pinfunction "VCCA_FPLL_AB6") (pintype "power_in"))
      (node (ref "D4") (pin "J24") (pinfunction "VCCA_FPLL_J24") (pintype "power_in"))
      (node (ref "D4") (pin "J8") (pinfunction "VCCA_FPLL_J8") (pintype "power_in"))
      (node (ref "D4") (pin "K6") (pinfunction "VCCA_FPLL_K6") (pintype "power_in"))
      (node (ref "D4") (pin "P6") (pinfunction "VCCA_FPLL_P6") (pintype "power_in"))
      (node (ref "D4") (pin "V6") (pinfunction "VCCA_FPLL_V6") (pintype "power_in"))
      (node (ref "D4") (pin "Y8") (pinfunction "VCCA_FPLL_Y8") (pintype "power_in"))
      (node (ref "L3") (pin "1") (pinfunction "1_1") (pintype "passive"))
    )
    (net (code "18") (name "/vccpgm") (class "Default")
      (node (ref "C109") (pin "2") (pinfunction "2_2") (pintype "passive"))
      (node (ref "C110") (pin "2") (pinfunction "2_2") (pintype "passive"))
      (node (ref "C95") (pin "2") (pinfunction "2_2") (pintype "passive"))
      (node (ref "C96") (pin "2") (pinfunction "2_2") (pintype "passive"))
      (node (ref "D4") (pin "AB24") (pinfunction "VCCPGM_AB24") (pintype "power_in"))
      (node (ref "D4") (pin "AC11") (pinfunction "VCCPGM_AC11") (pintype "power_in"))
      (node (ref "D4") (pin "AC8") (pinfunction "VCCIO3A_AC8") (pintype "power_in"))
      (node (ref "D4") (pin "AD11") (pinfunction "VCCIO3A_AD11") (pintype "power_in"))
      (node (ref "D4") (pin "F10") (pinfunction "VCCPGM_F10") (pintype "power_in"))
      (node (ref "D4") (pin "U10") (pinfunction "VCCIO3A_U10") (pintype "power_in"))
      (node (ref "D4") (pin "Y9") (pinfunction "VCCIO3A_Y9") (pintype "power_in"))
      (node (ref "L5") (pin "1") (pinfunction "1_1") (pintype "passive"))
      (node (ref "R25") (pin "1") (pinfunction "1_1") (pintype "passive"))
      (node (ref "R26") (pin "1") (pinfunction "1_1") (pintype "passive"))
      (node (ref "R27") (pin "2") (pinfunction "2_2") (pintype "passive"))
      (node (ref "R28") (pin "2") (pinfunction "2_2") (pintype "passive"))
      (node (ref "R29") (pin "2") (pinfunction "2_2") (pintype "passive"))
      (node (ref "R30") (pin "1") (pinfunction "1_1") (pintype "passive"))
      (node (ref "R31") (pin "1") (pinfunction "1_1") (pintype "passive"))
      (node (ref "R32") (pin "1") (pinfunction "1_1") (pintype "passive"))
      (node (ref "X1") (pin "4") (pintype "passive"))
    )
    (net (code "19") (name "Net-(D4I-MSEL1)") (class "Default")
      (node (ref "D4") (pin "P9") (pinfunction "MSEL1_P9") (pintype "input"))
      (node (ref "R28") (pin "1") (pinfunction "1_1") (pintype "passive"))
    )
    (net (code "20") (name "Net-(D4I-MSEL4)") (class "Default")
      (node (ref "D4") (pin "M7") (pinfunction "MSEL4_M7") (pintype "input"))
      (node (ref "R29") (pin "1") (pinfunction "1_1") (pintype "passive"))
    )
    (net (code "21") (name "unconnected-(D4I-AS_DATA1,_DATA1-PadAE5)") (class "Default")
      (node (ref "D4") (pin "AE5") (pinfunction "AS_DATA1,_DATA1_AE5") (pintype "bidirectional"))
    )
    (net (code "22") (name "unconnected-(D4I-AS_DATA2,_DATA2-PadAE7)") (class "Default")
      (node (ref "D4") (pin "AE7") (pinfunction "AS_DATA2,_DATA2_AE7") (pintype "bidirectional"))
    )
    (net (code "23") (name "unconnected-(D4I-AS_DATA3,_DATA3-PadAB7)") (class "Default")
      (node (ref "D4") (pin "AB7") (pinfunction "AS_DATA3,_DATA3_AB7") (pintype "bidirectional"))
    )
    (net (code "24") (name "unconnected-(D4I-nCSO,_DATA4-PadAA7)") (class "Default")
      (node (ref "D4") (pin "AA7") (pinfunction "nCSO,_DATA4_AA7") (pintype "output"))
    )
    (net (code "25") (name "unconnected-(X1-Pad6)") (class "Default")
      (node (ref "X1") (pin "6") (pintype "passive"))
    )
    (net (code "26") (name "unconnected-(X1-Pad7)") (class "Default")
      (node (ref "X1") (pin "7") (pintype "passive"))
    )
    (net (code "27") (name "unconnected-(X1-Pad8)") (class "Default")
      (node (ref "X1") (pin "8") (pintype "passive"))
    )
  )
)
